# DZ60_Demoboard_V10_DLN18703.net
KiCad netlist of a schematic drawn in EAGLE
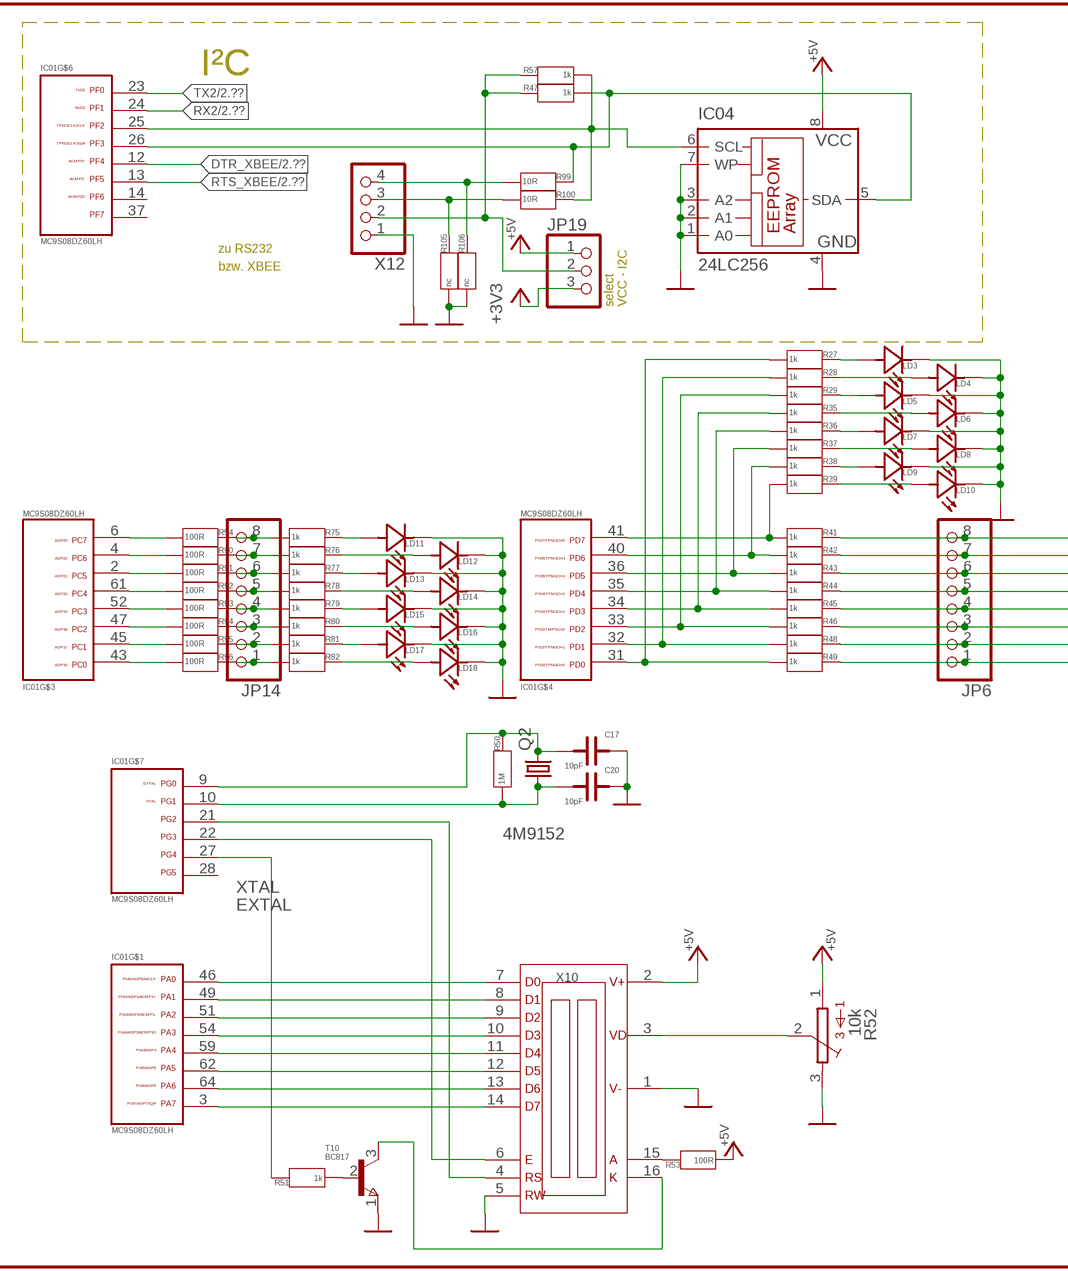
[diagram p0: schematic, sheet 1, part 1 of 2]
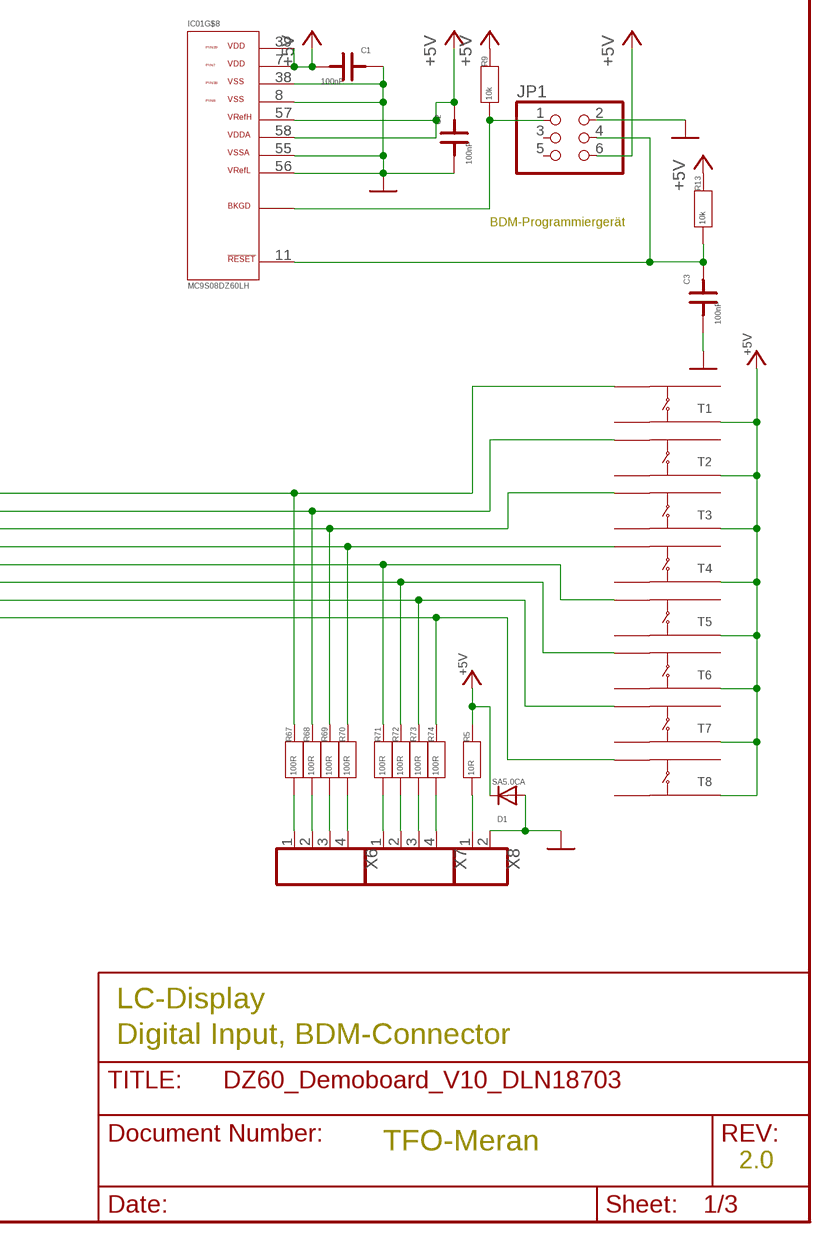
[diagram p1: schematic, sheet 1, part 2 of 2]
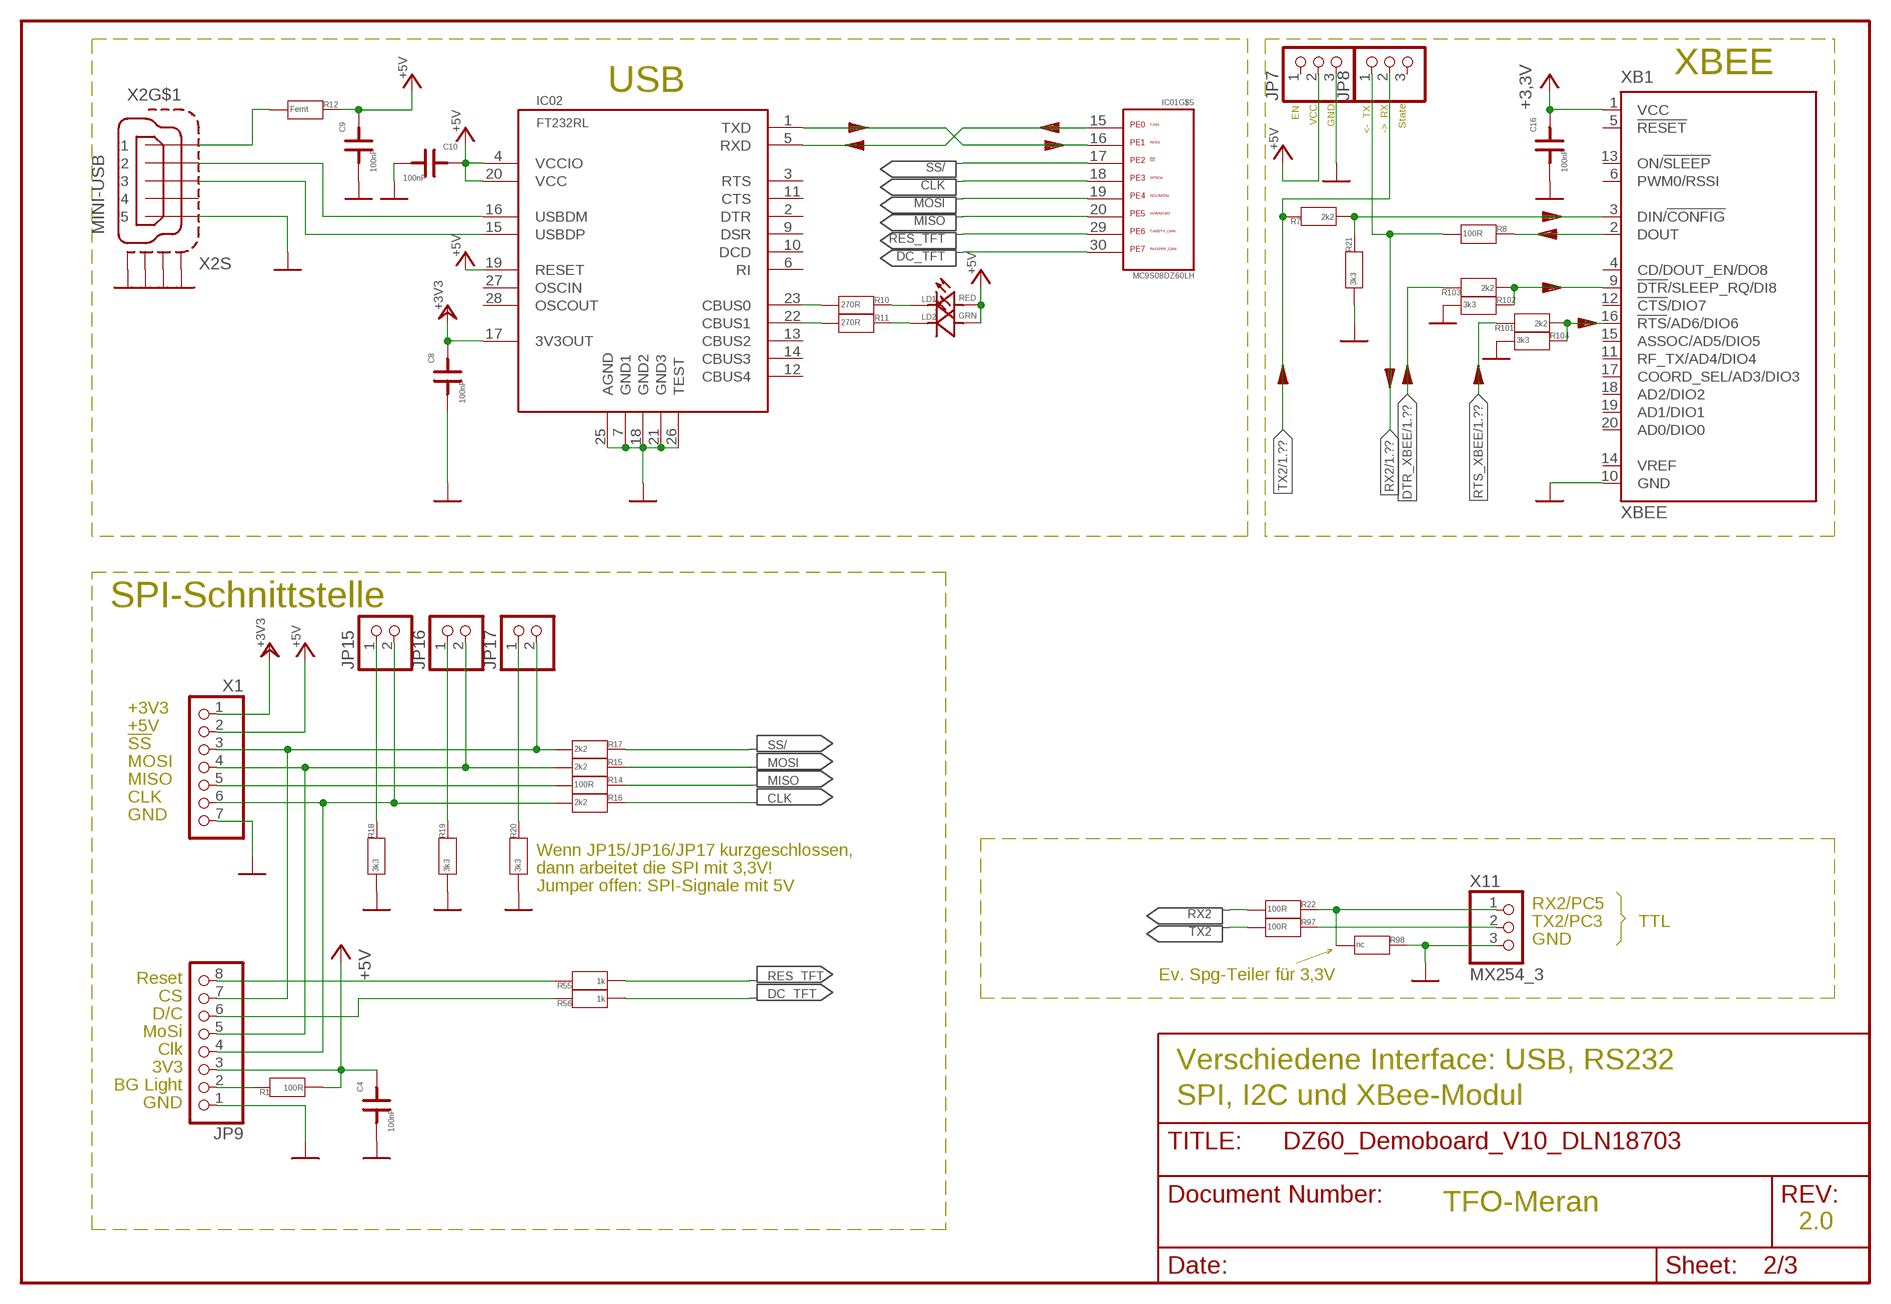
[diagram p2: schematic, sheet 2]
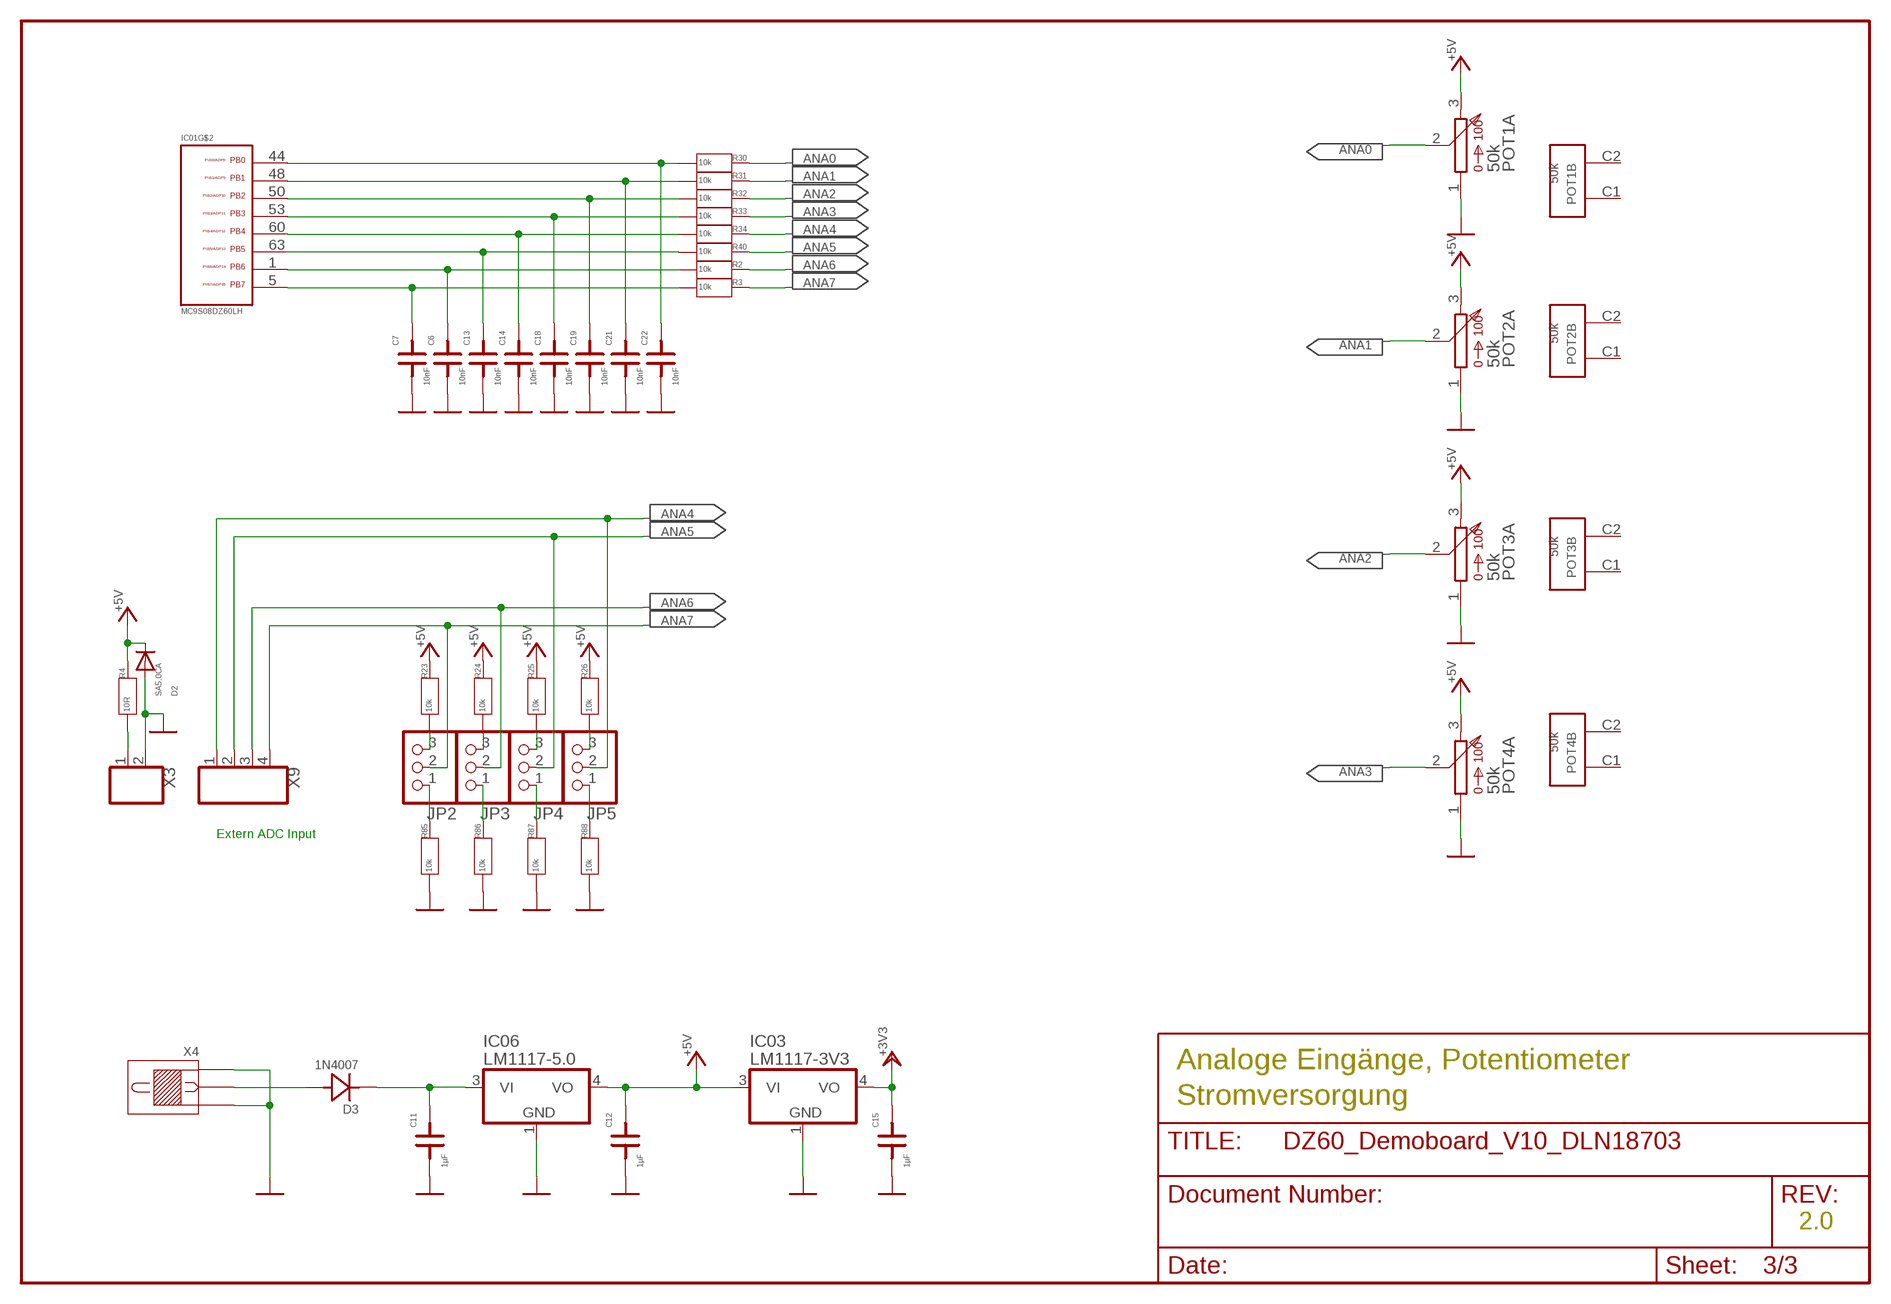
[diagram p3: schematic, sheet 3]

(export (version "E")
  (design (tool "Eeschema 10.0.6"))
  (components
    (comp (ref "C1")
      (value "100nF")
      (footprint "eagle-import:0805F")
      (libsource (lib "eagle-import") (part "C1"))
    )
    (comp (ref "C2")
      (value "100nF")
      (footprint "eagle-import:0805F")
      (libsource (lib "eagle-import") (part "C1"))
    )
    (comp (ref "C3")
      (value "100nF")
      (footprint "eagle-import:0805F")
      (libsource (lib "eagle-import") (part "C1"))
    )
    (comp (ref "C17")
      (value "10pF")
      (footprint "eagle-import:0805F")
      (libsource (lib "eagle-import") (part "C1"))
    )
    (comp (ref "C20")
      (value "10pF")
      (footprint "eagle-import:0805F")
      (libsource (lib "eagle-import") (part "C1"))
    )
    (comp (ref "D1")
      (value "SA5.0CA")
      (footprint "eagle-import:SMB")
      (libsource (lib "eagle-import") (part "DIODE-SMB"))
    )
    (comp (ref "IC01")
      (value "MC9S08DZ60LH")
      (footprint "eagle-import:LQFP64")
      (libsource (lib "eagle-import") (part "MC9S08DZ60LH"))
    )
    (comp (ref "IC04")
      (value "24LC256")
      (footprint "eagle-import:SO-08M")
      (libsource (lib "eagle-import") (part "24CSMLC256"))
    )
    (comp (ref "JP1")
      (value "PINHD-2X3")
      (footprint "eagle-import:2X03")
      (libsource (lib "eagle-import") (part "PINHD-2X3"))
    )
    (comp (ref "JP6")
      (value "PINHD-1X8")
      (footprint "eagle-import:1X08")
      (libsource (lib "eagle-import") (part "PINHD-1X8"))
    )
    (comp (ref "JP14")
      (value "PINHD-1X8")
      (footprint "eagle-import:1X08")
      (libsource (lib "eagle-import") (part "PINHD-1X8"))
    )
    (comp (ref "JP19")
      (value "PINHD-1X3")
      (footprint "eagle-import:1X03")
      (libsource (lib "eagle-import") (part "PINHD-1X3"))
    )
    (comp (ref "LD3")
      (value "LEDSMD")
      (footprint "eagle-import:0805LED")
      (libsource (lib "eagle-import") (part "LEDSMD"))
    )
    (comp (ref "LD4")
      (value "LEDSMD")
      (footprint "eagle-import:0805LED")
      (libsource (lib "eagle-import") (part "LEDSMD"))
    )
    (comp (ref "LD5")
      (value "LEDSMD")
      (footprint "eagle-import:0805LED")
      (libsource (lib "eagle-import") (part "LEDSMD"))
    )
    (comp (ref "LD6")
      (value "LEDSMD")
      (footprint "eagle-import:0805LED")
      (libsource (lib "eagle-import") (part "LEDSMD"))
    )
    (comp (ref "LD7")
      (value "LEDSMD")
      (footprint "eagle-import:0805LED")
      (libsource (lib "eagle-import") (part "LEDSMD"))
    )
    (comp (ref "LD8")
      (value "LEDSMD")
      (footprint "eagle-import:0805LED")
      (libsource (lib "eagle-import") (part "LEDSMD"))
    )
    (comp (ref "LD9")
      (value "LEDSMD")
      (footprint "eagle-import:0805LED")
      (libsource (lib "eagle-import") (part "LEDSMD"))
    )
    (comp (ref "LD10")
      (value "LEDSMD")
      (footprint "eagle-import:0805LED")
      (libsource (lib "eagle-import") (part "LEDSMD"))
    )
    (comp (ref "LD11")
      (value "LEDSMD")
      (footprint "eagle-import:0805LED")
      (libsource (lib "eagle-import") (part "LEDSMD"))
    )
    (comp (ref "LD12")
      (value "LEDSMD")
      (footprint "eagle-import:0805LED")
      (libsource (lib "eagle-import") (part "LEDSMD"))
    )
    (comp (ref "LD13")
      (value "LEDSMD")
      (footprint "eagle-import:0805LED")
      (libsource (lib "eagle-import") (part "LEDSMD"))
    )
    (comp (ref "LD14")
      (value "LEDSMD")
      (footprint "eagle-import:0805LED")
      (libsource (lib "eagle-import") (part "LEDSMD"))
    )
    (comp (ref "LD15")
      (value "LEDSMD")
      (footprint "eagle-import:0805LED")
      (libsource (lib "eagle-import") (part "LEDSMD"))
    )
    (comp (ref "LD16")
      (value "LEDSMD")
      (footprint "eagle-import:0805LED")
      (libsource (lib "eagle-import") (part "LEDSMD"))
    )
    (comp (ref "LD17")
      (value "LEDSMD")
      (footprint "eagle-import:0805LED")
      (libsource (lib "eagle-import") (part "LEDSMD"))
    )
    (comp (ref "LD18")
      (value "LEDSMD")
      (footprint "eagle-import:0805LED")
      (libsource (lib "eagle-import") (part "LEDSMD"))
    )
    (comp (ref "Q2")
      (value "4M9152")
      (footprint "eagle-import:HC49UP")
      (libsource (lib "eagle-import") (part "HC49UP"))
    )
    (comp (ref "R5")
      (value "10R")
      (footprint "eagle-import:0805")
      (libsource (lib "eagle-import") (part "R1"))
    )
    (comp (ref "R9")
      (value "10k")
      (footprint "eagle-import:0805")
      (libsource (lib "eagle-import") (part "R1"))
    )
    (comp (ref "R13")
      (value "10k")
      (footprint "eagle-import:0805")
      (libsource (lib "eagle-import") (part "R1"))
    )
    (comp (ref "R27")
      (value "1k")
      (footprint "eagle-import:0805")
      (libsource (lib "eagle-import") (part "R1"))
    )
    (comp (ref "R28")
      (value "1k")
      (footprint "eagle-import:0805")
      (libsource (lib "eagle-import") (part "R1"))
    )
    (comp (ref "R29")
      (value "1k")
      (footprint "eagle-import:0805")
      (libsource (lib "eagle-import") (part "R1"))
    )
    (comp (ref "R35")
      (value "1k")
      (footprint "eagle-import:0805")
      (libsource (lib "eagle-import") (part "R1"))
    )
    (comp (ref "R36")
      (value "1k")
      (footprint "eagle-import:0805")
      (libsource (lib "eagle-import") (part "R1"))
    )
    (comp (ref "R37")
      (value "1k")
      (footprint "eagle-import:0805")
      (libsource (lib "eagle-import") (part "R1"))
    )
    (comp (ref "R38")
      (value "1k")
      (footprint "eagle-import:0805")
      (libsource (lib "eagle-import") (part "R1"))
    )
    (comp (ref "R39")
      (value "1k")
      (footprint "eagle-import:0805")
      (libsource (lib "eagle-import") (part "R1"))
    )
    (comp (ref "R41")
      (value "1k")
      (footprint "eagle-import:0805")
      (libsource (lib "eagle-import") (part "R1"))
    )
    (comp (ref "R42")
      (value "1k")
      (footprint "eagle-import:0805")
      (libsource (lib "eagle-import") (part "R1"))
    )
    (comp (ref "R43")
      (value "1k")
      (footprint "eagle-import:0805")
      (libsource (lib "eagle-import") (part "R1"))
    )
    (comp (ref "R44")
      (value "1k")
      (footprint "eagle-import:0805")
      (libsource (lib "eagle-import") (part "R1"))
    )
    (comp (ref "R45")
      (value "1k")
      (footprint "eagle-import:0805")
      (libsource (lib "eagle-import") (part "R1"))
    )
    (comp (ref "R46")
      (value "1k")
      (footprint "eagle-import:0805")
      (libsource (lib "eagle-import") (part "R1"))
    )
    (comp (ref "R47")
      (value "1k")
      (footprint "eagle-import:0805")
      (libsource (lib "eagle-import") (part "R1"))
    )
    (comp (ref "R48")
      (value "1k")
      (footprint "eagle-import:0805")
      (libsource (lib "eagle-import") (part "R1"))
    )
    (comp (ref "R49")
      (value "1k")
      (footprint "eagle-import:0805")
      (libsource (lib "eagle-import") (part "R1"))
    )
    (comp (ref "R50")
      (value "1M")
      (footprint "eagle-import:0805")
      (libsource (lib "eagle-import") (part "R1"))
    )
    (comp (ref "R51")
      (value "1k")
      (footprint "eagle-import:0805")
      (libsource (lib "eagle-import") (part "R1"))
    )
    (comp (ref "R52")
      (value "10k")
      (footprint "eagle-import:S63X")
      (libsource (lib "eagle-import") (part "S63X"))
    )
    (comp (ref "R53")
      (value "100R")
      (footprint "eagle-import:0805")
      (libsource (lib "eagle-import") (part "R1"))
    )
    (comp (ref "R54")
      (value "100R")
      (footprint "eagle-import:0805")
      (libsource (lib "eagle-import") (part "R1"))
    )
    (comp (ref "R57")
      (value "1k")
      (footprint "eagle-import:0805")
      (libsource (lib "eagle-import") (part "R1"))
    )
    (comp (ref "R67")
      (value "100R")
      (footprint "eagle-import:0805")
      (libsource (lib "eagle-import") (part "R1"))
    )
    (comp (ref "R68")
      (value "100R")
      (footprint "eagle-import:0805")
      (libsource (lib "eagle-import") (part "R1"))
    )
    (comp (ref "R69")
      (value "100R")
      (footprint "eagle-import:0805")
      (libsource (lib "eagle-import") (part "R1"))
    )
    (comp (ref "R70")
      (value "100R")
      (footprint "eagle-import:0805")
      (libsource (lib "eagle-import") (part "R1"))
    )
    (comp (ref "R71")
      (value "100R")
      (footprint "eagle-import:0805")
      (libsource (lib "eagle-import") (part "R1"))
    )
    (comp (ref "R72")
      (value "100R")
      (footprint "eagle-import:0805")
      (libsource (lib "eagle-import") (part "R1"))
    )
    (comp (ref "R73")
      (value "100R")
      (footprint "eagle-import:0805")
      (libsource (lib "eagle-import") (part "R1"))
    )
    (comp (ref "R74")
      (value "100R")
      (footprint "eagle-import:0805")
      (libsource (lib "eagle-import") (part "R1"))
    )
    (comp (ref "R75")
      (value "1k")
      (footprint "eagle-import:0805")
      (libsource (lib "eagle-import") (part "R1"))
    )
    (comp (ref "R76")
      (value "1k")
      (footprint "eagle-import:0805")
      (libsource (lib "eagle-import") (part "R1"))
    )
    (comp (ref "R77")
      (value "1k")
      (footprint "eagle-import:0805")
      (libsource (lib "eagle-import") (part "R1"))
    )
    (comp (ref "R78")
      (value "1k")
      (footprint "eagle-import:0805")
      (libsource (lib "eagle-import") (part "R1"))
    )
    (comp (ref "R79")
      (value "1k")
      (footprint "eagle-import:0805")
      (libsource (lib "eagle-import") (part "R1"))
    )
    (comp (ref "R80")
      (value "1k")
      (footprint "eagle-import:0805")
      (libsource (lib "eagle-import") (part "R1"))
    )
    (comp (ref "R81")
      (value "1k")
      (footprint "eagle-import:0805")
      (libsource (lib "eagle-import") (part "R1"))
    )
    (comp (ref "R82")
      (value "1k")
      (footprint "eagle-import:0805")
      (libsource (lib "eagle-import") (part "R1"))
    )
    (comp (ref "R90")
      (value "100R")
      (footprint "eagle-import:0805")
      (libsource (lib "eagle-import") (part "R1"))
    )
    (comp (ref "R91")
      (value "100R")
      (footprint "eagle-import:0805")
      (libsource (lib "eagle-import") (part "R1"))
    )
    (comp (ref "R92")
      (value "100R")
      (footprint "eagle-import:0805")
      (libsource (lib "eagle-import") (part "R1"))
    )
    (comp (ref "R93")
      (value "100R")
      (footprint "eagle-import:0805")
      (libsource (lib "eagle-import") (part "R1"))
    )
    (comp (ref "R94")
      (value "100R")
      (footprint "eagle-import:0805")
      (libsource (lib "eagle-import") (part "R1"))
    )
    (comp (ref "R95")
      (value "100R")
      (footprint "eagle-import:0805")
      (libsource (lib "eagle-import") (part "R1"))
    )
    (comp (ref "R96")
      (value "100R")
      (footprint "eagle-import:0805")
      (libsource (lib "eagle-import") (part "R1"))
    )
    (comp (ref "R99")
      (value "10R")
      (footprint "eagle-import:0805")
      (libsource (lib "eagle-import") (part "R1"))
    )
    (comp (ref "R100")
      (value "10R")
      (footprint "eagle-import:0805")
      (libsource (lib "eagle-import") (part "R1"))
    )
    (comp (ref "R105")
      (value "nc")
      (footprint "eagle-import:0805")
      (libsource (lib "eagle-import") (part "R1"))
    )
    (comp (ref "R106")
      (value "nc")
      (footprint "eagle-import:0805")
      (libsource (lib "eagle-import") (part "R1"))
    )
    (comp (ref "T1")
      (value "TASTERTHT")
      (footprint "eagle-import:TASTE_THT")
      (libsource (lib "eagle-import") (part "TASTERTHT"))
    )
    (comp (ref "T2")
      (value "TASTERTHT")
      (footprint "eagle-import:TASTE_THT")
      (libsource (lib "eagle-import") (part "TASTERTHT"))
    )
    (comp (ref "T3")
      (value "TASTERTHT")
      (footprint "eagle-import:TASTE_THT")
      (libsource (lib "eagle-import") (part "TASTERTHT"))
    )
    (comp (ref "T4")
      (value "TASTERTHT")
      (footprint "eagle-import:TASTE_THT")
      (libsource (lib "eagle-import") (part "TASTERTHT"))
    )
    (comp (ref "T5")
      (value "TASTERTHT")
      (footprint "eagle-import:TASTE_THT")
      (libsource (lib "eagle-import") (part "TASTERTHT"))
    )
    (comp (ref "T6")
      (value "TASTERTHT")
      (footprint "eagle-import:TASTE_THT")
      (libsource (lib "eagle-import") (part "TASTERTHT"))
    )
    (comp (ref "T7")
      (value "TASTERTHT")
      (footprint "eagle-import:TASTE_THT")
      (libsource (lib "eagle-import") (part "TASTERTHT"))
    )
    (comp (ref "T8")
      (value "TASTERTHT")
      (footprint "eagle-import:TASTE_THT")
      (libsource (lib "eagle-import") (part "TASTERTHT"))
    )
    (comp (ref "T10")
      (value "BC817")
      (footprint "eagle-import:SOT-23")
      (libsource (lib "eagle-import") (part "BC817"))
    )
    (comp (ref "X6")
      (value "KLEMME4")
      (footprint "eagle-import:KLEMME4")
      (libsource (lib "eagle-import") (part "KLEMME4"))
    )
    (comp (ref "X7")
      (value "KLEMME4")
      (footprint "eagle-import:KLEMME4")
      (libsource (lib "eagle-import") (part "KLEMME4"))
    )
    (comp (ref "X8")
      (value "KLEMME2")
      (footprint "eagle-import:KLEMME2")
      (libsource (lib "eagle-import") (part "KLEMME2"))
    )
    (comp (ref "X10")
      (value "FDCC1602G")
      (footprint "eagle-import:FDCC1602G")
      (libsource (lib "eagle-import") (part "FDCC1602G"))
    )
    (comp (ref "X12")
      (value "MX254_4")
      (footprint "eagle-import:MX4")
      (libsource (lib "eagle-import") (part "MX254_4"))
    )
    (comp (ref "C4")
      (value "100nF")
      (footprint "eagle-import:0805F")
      (libsource (lib "eagle-import") (part "C1"))
    )
    (comp (ref "C8")
      (value "100nF")
      (footprint "eagle-import:0805F")
      (libsource (lib "eagle-import") (part "C1"))
    )
    (comp (ref "C9")
      (value "100nF")
      (footprint "eagle-import:0805F")
      (libsource (lib "eagle-import") (part "C1"))
    )
    (comp (ref "C10")
      (value "100nF")
      (footprint "eagle-import:0805F")
      (libsource (lib "eagle-import") (part "C1"))
    )
    (comp (ref "C16")
      (value "100nF")
      (footprint "eagle-import:0805F")
      (libsource (lib "eagle-import") (part "C1"))
    )
    (comp (ref "IC02")
      (value "FT232RL")
      (footprint "eagle-import:SSOP28")
      (libsource (lib "eagle-import") (part "FTDI232RL"))
    )
    (comp (ref "JP7")
      (value "PINHD-1X3")
      (footprint "eagle-import:1X03")
      (libsource (lib "eagle-import") (part "PINHD-1X3"))
    )
    (comp (ref "JP8")
      (value "PINHD-1X3")
      (footprint "eagle-import:1X03")
      (libsource (lib "eagle-import") (part "PINHD-1X3"))
    )
    (comp (ref "JP9")
      (value "PINHD-1X8")
      (footprint "eagle-import:1X08")
      (libsource (lib "eagle-import") (part "PINHD-1X8"))
    )
    (comp (ref "JP15")
      (value "PINHD-1X2")
      (footprint "eagle-import:1X02")
      (libsource (lib "eagle-import") (part "PINHD-1X2"))
    )
    (comp (ref "JP16")
      (value "PINHD-1X2")
      (footprint "eagle-import:1X02")
      (libsource (lib "eagle-import") (part "PINHD-1X2"))
    )
    (comp (ref "JP17")
      (value "PINHD-1X2")
      (footprint "eagle-import:1X02")
      (libsource (lib "eagle-import") (part "PINHD-1X2"))
    )
    (comp (ref "LD1")
      (value "RED")
      (footprint "eagle-import:0805LED")
      (libsource (lib "eagle-import") (part "LEDSMD"))
    )
    (comp (ref "LD2")
      (value "GRN")
      (footprint "eagle-import:0805LED")
      (libsource (lib "eagle-import") (part "LEDSMD"))
    )
    (comp (ref "R1")
      (value "100R")
      (footprint "eagle-import:0805")
      (libsource (lib "eagle-import") (part "R1"))
    )
    (comp (ref "R7")
      (value "2k2")
      (footprint "eagle-import:0805")
      (libsource (lib "eagle-import") (part "R1"))
    )
    (comp (ref "R8")
      (value "100R")
      (footprint "eagle-import:0805")
      (libsource (lib "eagle-import") (part "R1"))
    )
    (comp (ref "R10")
      (value "270R")
      (footprint "eagle-import:0805")
      (libsource (lib "eagle-import") (part "R1"))
    )
    (comp (ref "R11")
      (value "270R")
      (footprint "eagle-import:0805")
      (libsource (lib "eagle-import") (part "R1"))
    )
    (comp (ref "R12")
      (value "Ferrit")
      (footprint "eagle-import:1206")
      (libsource (lib "eagle-import") (part "R2"))
    )
    (comp (ref "R14")
      (value "100R")
      (footprint "eagle-import:0805")
      (libsource (lib "eagle-import") (part "R1"))
    )
    (comp (ref "R15")
      (value "2k2")
      (footprint "eagle-import:0805")
      (libsource (lib "eagle-import") (part "R1"))
    )
    (comp (ref "R16")
      (value "2k2")
      (footprint "eagle-import:0805")
      (libsource (lib "eagle-import") (part "R1"))
    )
    (comp (ref "R17")
      (value "2k2")
      (footprint "eagle-import:0805")
      (libsource (lib "eagle-import") (part "R1"))
    )
    (comp (ref "R18")
      (value "3k3")
      (footprint "eagle-import:0805")
      (libsource (lib "eagle-import") (part "R1"))
    )
    (comp (ref "R19")
      (value "3k3")
      (footprint "eagle-import:0805")
      (libsource (lib "eagle-import") (part "R1"))
    )
    (comp (ref "R20")
      (value "3k3")
      (footprint "eagle-import:0805")
      (libsource (lib "eagle-import") (part "R1"))
    )
    (comp (ref "R21")
      (value "3k3")
      (footprint "eagle-import:0805")
      (libsource (lib "eagle-import") (part "R1"))
    )
    (comp (ref "R22")
      (value "100R")
      (footprint "eagle-import:0805")
      (libsource (lib "eagle-import") (part "R1"))
    )
    (comp (ref "R55")
      (value "1k")
      (footprint "eagle-import:0805")
      (libsource (lib "eagle-import") (part "R1"))
    )
    (comp (ref "R56")
      (value "1k")
      (footprint "eagle-import:0805")
      (libsource (lib "eagle-import") (part "R1"))
    )
    (comp (ref "R97")
      (value "100R")
      (footprint "eagle-import:0805")
      (libsource (lib "eagle-import") (part "R1"))
    )
    (comp (ref "R98")
      (value "nc")
      (footprint "eagle-import:0805")
      (libsource (lib "eagle-import") (part "R1"))
    )
    (comp (ref "R101")
      (value "2k2")
      (footprint "eagle-import:0805")
      (libsource (lib "eagle-import") (part "R1"))
    )
    (comp (ref "R102")
      (value "3k3")
      (footprint "eagle-import:0805")
      (libsource (lib "eagle-import") (part "R1"))
    )
    (comp (ref "R103")
      (value "2k2")
      (footprint "eagle-import:0805")
      (libsource (lib "eagle-import") (part "R1"))
    )
    (comp (ref "R104")
      (value "3k3")
      (footprint "eagle-import:0805")
      (libsource (lib "eagle-import") (part "R1"))
    )
    (comp (ref "X1")
      (value "MX254_7")
      (footprint "eagle-import:MX7")
      (libsource (lib "eagle-import") (part "MX254_7"))
    )
    (comp (ref "X2")
      (value "MINI-USB")
      (footprint "eagle-import:32005-201")
      (libsource (lib "eagle-import") (part "MINI-USB-SCHIELD-32005-201"))
    )
    (comp (ref "X11")
      (value "MX254_3")
      (footprint "eagle-import:MX3")
      (libsource (lib "eagle-import") (part "MX254_3"))
    )
    (comp (ref "XB1")
      (value "XBEE")
      (footprint "eagle-import:XBEE")
      (fields (field (name "MPN") "XBP24-Z7UIT-004"))
      (libsource (lib "eagle-import") (part "XBEE"))
    )
    (comp (ref "C6")
      (value "10nF")
      (footprint "eagle-import:0805F")
      (libsource (lib "eagle-import") (part "C1"))
    )
    (comp (ref "C7")
      (value "10nF")
      (footprint "eagle-import:0805F")
      (libsource (lib "eagle-import") (part "C1"))
    )
    (comp (ref "C11")
      (value "1µF")
      (footprint "eagle-import:0805F")
      (libsource (lib "eagle-import") (part "C1"))
    )
    (comp (ref "C12")
      (value "1µF")
      (footprint "eagle-import:0805F")
      (libsource (lib "eagle-import") (part "C1"))
    )
    (comp (ref "C13")
      (value "10nF")
      (footprint "eagle-import:0805F")
      (libsource (lib "eagle-import") (part "C1"))
    )
    (comp (ref "C14")
      (value "10nF")
      (footprint "eagle-import:0805F")
      (libsource (lib "eagle-import") (part "C1"))
    )
    (comp (ref "C15")
      (value "1µF")
      (footprint "eagle-import:0805F")
      (libsource (lib "eagle-import") (part "C1"))
    )
    (comp (ref "C18")
      (value "10nF")
      (footprint "eagle-import:0805F")
      (libsource (lib "eagle-import") (part "C1"))
    )
    (comp (ref "C19")
      (value "10nF")
      (footprint "eagle-import:0805F")
      (libsource (lib "eagle-import") (part "C1"))
    )
    (comp (ref "C21")
      (value "10nF")
      (footprint "eagle-import:0805F")
      (libsource (lib "eagle-import") (part "C1"))
    )
    (comp (ref "C22")
      (value "10nF")
      (footprint "eagle-import:0805F")
      (libsource (lib "eagle-import") (part "C1"))
    )
    (comp (ref "D2")
      (value "SA5.0CA")
      (footprint "eagle-import:SMB")
      (libsource (lib "eagle-import") (part "DIODE-SMB"))
    )
    (comp (ref "D3")
      (value "1N4007")
      (footprint "eagle-import:MELF_B")
      (libsource (lib "eagle-import") (part "DHCMELF"))
    )
    (comp (ref "IC03")
      (value "LM1117-3V3")
      (footprint "eagle-import:DPAK")
      (libsource (lib "eagle-import") (part "LM1117DT"))
    )
    (comp (ref "IC06")
      (value "LM1117-5.0")
      (footprint "eagle-import:DPAK")
      (libsource (lib "eagle-import") (part "LM1117DT"))
    )
    (comp (ref "JP2")
      (value "PINHD-1X3")
      (footprint "eagle-import:1X03")
      (libsource (lib "eagle-import") (part "PINHD-1X3"))
    )
    (comp (ref "JP3")
      (value "PINHD-1X3")
      (footprint "eagle-import:1X03")
      (libsource (lib "eagle-import") (part "PINHD-1X3"))
    )
    (comp (ref "JP4")
      (value "PINHD-1X3")
      (footprint "eagle-import:1X03")
      (libsource (lib "eagle-import") (part "PINHD-1X3"))
    )
    (comp (ref "JP5")
      (value "PINHD-1X3")
      (footprint "eagle-import:1X03")
      (libsource (lib "eagle-import") (part "PINHD-1X3"))
    )
    (comp (ref "POT1")
      (value "50k")
      (footprint "eagle-import:ALPS_VERTICAL")
      (libsource (lib "eagle-import") (part "ALPSVERT"))
    )
    (comp (ref "POT2")
      (value "50k")
      (footprint "eagle-import:ALPS_VERTICAL")
      (libsource (lib "eagle-import") (part "ALPSVERT"))
    )
    (comp (ref "POT3")
      (value "50k")
      (footprint "eagle-import:ALPS_VERTICAL")
      (libsource (lib "eagle-import") (part "ALPSVERT"))
    )
    (comp (ref "POT4")
      (value "50k")
      (footprint "eagle-import:ALPS_VERTICAL")
      (libsource (lib "eagle-import") (part "ALPSVERT"))
    )
    (comp (ref "R2")
      (value "10k")
      (footprint "eagle-import:0805")
      (libsource (lib "eagle-import") (part "R1"))
    )
    (comp (ref "R3")
      (value "10k")
      (footprint "eagle-import:0805")
      (libsource (lib "eagle-import") (part "R1"))
    )
    (comp (ref "R4")
      (value "10R")
      (footprint "eagle-import:0805")
      (libsource (lib "eagle-import") (part "R1"))
    )
    (comp (ref "R23")
      (value "10k")
      (footprint "eagle-import:0805")
      (libsource (lib "eagle-import") (part "R1"))
    )
    (comp (ref "R24")
      (value "10k")
      (footprint "eagle-import:0805")
      (libsource (lib "eagle-import") (part "R1"))
    )
    (comp (ref "R25")
      (value "10k")
      (footprint "eagle-import:0805")
      (libsource (lib "eagle-import") (part "R1"))
    )
    (comp (ref "R26")
      (value "10k")
      (footprint "eagle-import:0805")
      (libsource (lib "eagle-import") (part "R1"))
    )
    (comp (ref "R30")
      (value "10k")
      (footprint "eagle-import:0805")
      (libsource (lib "eagle-import") (part "R1"))
    )
    (comp (ref "R31")
      (value "10k")
      (footprint "eagle-import:0805")
      (libsource (lib "eagle-import") (part "R1"))
    )
    (comp (ref "R32")
      (value "10k")
      (footprint "eagle-import:0805")
      (libsource (lib "eagle-import") (part "R1"))
    )
    (comp (ref "R33")
      (value "10k")
      (footprint "eagle-import:0805")
      (libsource (lib "eagle-import") (part "R1"))
    )
    (comp (ref "R34")
      (value "10k")
      (footprint "eagle-import:0805")
      (libsource (lib "eagle-import") (part "R1"))
    )
    (comp (ref "R40")
      (value "10k")
      (footprint "eagle-import:0805")
      (libsource (lib "eagle-import") (part "R1"))
    )
    (comp (ref "R85")
      (value "10k")
      (footprint "eagle-import:0805")
      (libsource (lib "eagle-import") (part "R1"))
    )
    (comp (ref "R86")
      (value "10k")
      (footprint "eagle-import:0805")
      (libsource (lib "eagle-import") (part "R1"))
    )
    (comp (ref "R87")
      (value "10k")
      (footprint "eagle-import:0805")
      (libsource (lib "eagle-import") (part "R1"))
    )
    (comp (ref "R88")
      (value "10k")
      (footprint "eagle-import:0805")
      (libsource (lib "eagle-import") (part "R1"))
    )
    (comp (ref "X3")
      (value "KLEMME2")
      (footprint "eagle-import:KLEMME2")
      (libsource (lib "eagle-import") (part "KLEMME2"))
    )
    (comp (ref "X4")
      (value "SPP")
      (footprint "eagle-import:SPP")
      (libsource (lib "eagle-import") (part "SPP"))
    )
    (comp (ref "X9")
      (value "KLEMME4")
      (footprint "eagle-import:KLEMME4")
      (libsource (lib "eagle-import") (part "KLEMME4"))
    )
  )
  (nets
    (net (code "1") (name "+3V3") (class "Default")
      (node (ref "C15") (pin "2") (pinfunction "2_2") (pintype "bidirectional"))
      (node (ref "C16") (pin "2") (pinfunction "2_2") (pintype "bidirectional"))
      (node (ref "C8") (pin "2") (pinfunction "2_2") (pintype "bidirectional"))
      (node (ref "IC02") (pin "17") (pinfunction "3V3OUT_17") (pintype "bidirectional"))
      (node (ref "IC03") (pin "4") (pinfunction "VO_4") (pintype "output"))
      (node (ref "JP19") (pin "3") (pinfunction "3_3") (pintype "passive"))
      (node (ref "X1") (pin "1") (pinfunction "1_1") (pintype "passive"))
      (node (ref "XB1") (pin "1") (pinfunction "VCC_1") (pintype "power_in"))
    )
    (net (code "2") (name "+5V") (class "Default")
      (node (ref "C1") (pin "1") (pinfunction "1_1") (pintype "bidirectional"))
      (node (ref "C10") (pin "2") (pinfunction "2_2") (pintype "bidirectional"))
      (node (ref "C12") (pin "2") (pinfunction "2_2") (pintype "bidirectional"))
      (node (ref "C2") (pin "2") (pinfunction "2_2") (pintype "bidirectional"))
      (node (ref "C4") (pin "2") (pinfunction "2_2") (pintype "bidirectional"))
      (node (ref "C9") (pin "2") (pinfunction "2_2") (pintype "bidirectional"))
      (node (ref "D1") (pin "C") (pinfunction "C_C") (pintype "passive"))
      (node (ref "D2") (pin "C") (pinfunction "C_C") (pintype "passive"))
      (node (ref "IC01") (pin "39") (pinfunction "VDD_PIN39_39") (pintype "bidirectional"))
      (node (ref "IC01") (pin "57") (pinfunction "VREFH_57") (pintype "bidirectional"))
      (node (ref "IC01") (pin "58") (pinfunction "VDDA_58") (pintype "bidirectional"))
      (node (ref "IC01") (pin "7") (pinfunction "VDD_PIN7_7") (pintype "bidirectional"))
      (node (ref "IC02") (pin "19") (pinfunction "RESET_19") (pintype "bidirectional"))
      (node (ref "IC02") (pin "20") (pinfunction "VCC_20") (pintype "bidirectional"))
      (node (ref "IC02") (pin "4") (pinfunction "VCCIO_4") (pintype "bidirectional"))
      (node (ref "IC03") (pin "3") (pinfunction "VI_3") (pintype "input"))
      (node (ref "IC04") (pin "8") (pinfunction "VCC_8") (pintype "power_in"))
      (node (ref "IC06") (pin "4") (pinfunction "VO_4") (pintype "output"))
      (node (ref "JP1") (pin "6") (pinfunction "6_6") (pintype "passive"))
      (node (ref "JP19") (pin "1") (pinfunction "1_1") (pintype "passive"))
      (node (ref "JP7") (pin "2") (pinfunction "2_2") (pintype "passive"))
      (node (ref "JP9") (pin "3") (pinfunction "3_3") (pintype "passive"))
      (node (ref "LD1") (pin "A") (pinfunction "2_A") (pintype "bidirectional"))
      (node (ref "LD2") (pin "A") (pinfunction "2_A") (pintype "bidirectional"))
      (node (ref "POT1") (pin "3") (pinfunction "3_3") (pintype "passive"))
      (node (ref "POT2") (pin "3") (pinfunction "3_3") (pintype "passive"))
      (node (ref "POT3") (pin "3") (pinfunction "3_3") (pintype "passive"))
      (node (ref "POT4") (pin "3") (pinfunction "3_3") (pintype "passive"))
      (node (ref "R1") (pin "1") (pinfunction "1_1") (pintype "bidirectional"))
      (node (ref "R12") (pin "2") (pinfunction "2_2") (pintype "bidirectional"))
      (node (ref "R13") (pin "2") (pinfunction "2_2") (pintype "bidirectional"))
      (node (ref "R23") (pin "2") (pinfunction "2_2") (pintype "bidirectional"))
      (node (ref "R24") (pin "2") (pinfunction "2_2") (pintype "bidirectional"))
      (node (ref "R25") (pin "2") (pinfunction "2_2") (pintype "bidirectional"))
      (node (ref "R26") (pin "2") (pinfunction "2_2") (pintype "bidirectional"))
      (node (ref "R4") (pin "2") (pinfunction "2_2") (pintype "bidirectional"))
      (node (ref "R5") (pin "2") (pinfunction "2_2") (pintype "bidirectional"))
      (node (ref "R52") (pin "1") (pinfunction "1_1") (pintype "passive"))
      (node (ref "R53") (pin "1") (pinfunction "1_1") (pintype "bidirectional"))
      (node (ref "R9") (pin "2") (pinfunction "2_2") (pintype "bidirectional"))
      (node (ref "T1") (pin "A1") (pinfunction "A1_A1") (pintype "bidirectional"))
      (node (ref "T2") (pin "A1") (pinfunction "A1_A1") (pintype "bidirectional"))
      (node (ref "T3") (pin "A1") (pinfunction "A1_A1") (pintype "bidirectional"))
      (node (ref "T4") (pin "A1") (pinfunction "A1_A1") (pintype "bidirectional"))
      (node (ref "T5") (pin "A1") (pinfunction "A1_A1") (pintype "bidirectional"))
      (node (ref "T6") (pin "A1") (pinfunction "A1_A1") (pintype "bidirectional"))
      (node (ref "T7") (pin "A1") (pinfunction "A1_A1") (pintype "bidirectional"))
      (node (ref "T8") (pin "A1") (pinfunction "A1_A1") (pintype "bidirectional"))
      (node (ref "X1") (pin "2") (pinfunction "2_2") (pintype "passive"))
      (node (ref "X10") (pin "2") (pinfunction "V+_2") (pintype "bidirectional"))
    )
    (net (code "3") (name "ANA0") (class "Default")
      (node (ref "POT1") (pin "2") (pinfunction "2_2") (pintype "passive"))
      (node (ref "R30") (pin "2") (pinfunction "2_2") (pintype "bidirectional"))
    )
    (net (code "4") (name "ANA1") (class "Default")
      (node (ref "POT2") (pin "2") (pinfunction "2_2") (pintype "passive"))
      (node (ref "R31") (pin "2") (pinfunction "2_2") (pintype "bidirectional"))
    )
    (net (code "5") (name "ANA2") (class "Default")
      (node (ref "POT3") (pin "2") (pinfunction "2_2") (pintype "passive"))
      (node (ref "R32") (pin "2") (pinfunction "2_2") (pintype "bidirectional"))
    )
    (net (code "6") (name "ANA3") (class "Default")
      (node (ref "POT4") (pin "2") (pinfunction "2_2") (pintype "passive"))
      (node (ref "R33") (pin "2") (pinfunction "2_2") (pintype "bidirectional"))
    )
    (net (code "7") (name "ANA4") (class "Default")
      (node (ref "JP5") (pin "2") (pinfunction "2_2") (pintype "passive"))
      (node (ref "R34") (pin "2") (pinfunction "2_2") (pintype "bidirectional"))
      (node (ref "X9") (pin "1") (pinfunction "1_1") (pintype "bidirectional"))
    )
    (net (code "8") (name "ANA5") (class "Default")
      (node (ref "JP4") (pin "2") (pinfunction "2_2") (pintype "passive"))
      (node (ref "R40") (pin "2") (pinfunction "2_2") (pintype "bidirectional"))
      (node (ref "X9") (pin "2") (pinfunction "2_2") (pintype "bidirectional"))
    )
    (net (code "9") (name "ANA6") (class "Default")
      (node (ref "JP3") (pin "2") (pinfunction "2_2") (pintype "passive"))
      (node (ref "R2") (pin "2") (pinfunction "2_2") (pintype "bidirectional"))
      (node (ref "X9") (pin "3") (pinfunction "3_3") (pintype "bidirectional"))
    )
    (net (code "10") (name "ANA7") (class "Default")
      (node (ref "JP2") (pin "2") (pinfunction "2_2") (pintype "passive"))
      (node (ref "R3") (pin "2") (pinfunction "2_2") (pintype "bidirectional"))
      (node (ref "X9") (pin "4") (pinfunction "4_4") (pintype "bidirectional"))
    )
    (net (code "11") (name "CLK") (class "Default")
      (node (ref "IC01") (pin "18") (pinfunction "PE3_18") (pintype "bidirectional"))
      (node (ref "R16") (pin "2") (pinfunction "2_2") (pintype "bidirectional"))
    )
    (net (code "12") (name "DC_TFT") (class "Default")
      (node (ref "IC01") (pin "30") (pinfunction "PE7_30") (pintype "bidirectional"))
      (node (ref "R56") (pin "1") (pinfunction "1_1") (pintype "bidirectional"))
    )
    (net (code "13") (name "DTR_XBEE") (class "Default")
      (node (ref "IC01") (pin "12") (pinfunction "PF4_12") (pintype "bidirectional"))
      (node (ref "R103") (pin "2") (pinfunction "2_2") (pintype "bidirectional"))
    )
    (net (code "14") (name "EXTAL") (class "Default")
      (node (ref "C20") (pin "1") (pinfunction "1_1") (pintype "bidirectional"))
      (node (ref "IC01") (pin "10") (pinfunction "PG1_10") (pintype "bidirectional"))
      (node (ref "Q2") (pin "1") (pinfunction "1_1") (pintype "passive"))
      (node (ref "R50") (pin "1") (pinfunction "1_1") (pintype "bidirectional"))
    )
    (net (code "15") (name "GND") (class "Default")
      (node (ref "C1") (pin "2") (pinfunction "2_2") (pintype "bidirectional"))
      (node (ref "C10") (pin "1") (pinfunction "1_1") (pintype "bidirectional"))
      (node (ref "C11") (pin "1") (pinfunction "1_1") (pintype "bidirectional"))
      (node (ref "C12") (pin "1") (pinfunction "1_1") (pintype "bidirectional"))
      (node (ref "C13") (pin "1") (pinfunction "1_1") (pintype "bidirectional"))
      (node (ref "C14") (pin "1") (pinfunction "1_1") (pintype "bidirectional"))
      (node (ref "C15") (pin "1") (pinfunction "1_1") (pintype "bidirectional"))
      (node (ref "C16") (pin "1") (pinfunction "1_1") (pintype "bidirectional"))
      (node (ref "C17") (pin "2") (pinfunction "2_2") (pintype "bidirectional"))
      (node (ref "C18") (pin "1") (pinfunction "1_1") (pintype "bidirectional"))
      (node (ref "C19") (pin "1") (pinfunction "1_1") (pintype "bidirectional"))
      (node (ref "C2") (pin "1") (pinfunction "1_1") (pintype "bidirectional"))
      (node (ref "C20") (pin "2") (pinfunction "2_2") (pintype "bidirectional"))
      (node (ref "C21") (pin "1") (pinfunction "1_1") (pintype "bidirectional"))
      (node (ref "C22") (pin "1") (pinfunction "1_1") (pintype "bidirectional"))
      (node (ref "C3") (pin "1") (pinfunction "1_1") (pintype "bidirectional"))
      (node (ref "C4") (pin "1") (pinfunction "1_1") (pintype "bidirectional"))
      (node (ref "C6") (pin "1") (pinfunction "1_1") (pintype "bidirectional"))
      (node (ref "C7") (pin "1") (pinfunction "1_1") (pintype "bidirectional"))
      (node (ref "C8") (pin "1") (pinfunction "1_1") (pintype "bidirectional"))
      (node (ref "C9") (pin "1") (pinfunction "1_1") (pintype "bidirectional"))
      (node (ref "D1") (pin "A") (pinfunction "A_A") (pintype "passive"))
      (node (ref "D2") (pin "A") (pinfunction "A_A") (pintype "passive"))
      (node (ref "IC01") (pin "38") (pinfunction "VSS_PIN38_38") (pintype "bidirectional"))
      (node (ref "IC01") (pin "55") (pinfunction "VSSA_55") (pintype "bidirectional"))
      (node (ref "IC01") (pin "56") (pinfunction "VREFL_56") (pintype "bidirectional"))
      (node (ref "IC01") (pin "8") (pinfunction "VSS_PIN8_8") (pintype "bidirectional"))
      (node (ref "IC02") (pin "18") (pinfunction "GND2_18") (pintype "bidirectional"))
      (node (ref "IC02") (pin "21") (pinfunction "GND3_21") (pintype "bidirectional"))
      (node (ref "IC02") (pin "25") (pinfunction "AGND_25") (pintype "bidirectional"))
      (node (ref "IC02") (pin "26") (pinfunction "TEST_26") (pintype "bidirectional"))
      (node (ref "IC02") (pin "7") (pinfunction "GND1_7") (pintype "bidirectional"))
      (node (ref "IC03") (pin "1") (pinfunction "GND_1") (pintype "input"))
      (node (ref "IC04") (pin "1") (pinfunction "A0_1") (pintype "input"))
      (node (ref "IC04") (pin "2") (pinfunction "A1_2") (pintype "input"))
      (node (ref "IC04") (pin "3") (pinfunction "A2_3") (pintype "input"))
      (node (ref "IC04") (pin "4") (pinfunction "GND_4") (pintype "power_in"))
      (node (ref "IC04") (pin "7") (pinfunction "WP_7") (pintype "input"))
      (node (ref "IC06") (pin "1") (pinfunction "GND_1") (pintype "input"))
      (node (ref "JP1") (pin "2") (pinfunction "2_2") (pintype "passive"))
      (node (ref "JP7") (pin "3") (pinfunction "3_3") (pintype "passive"))
      (node (ref "JP9") (pin "1") (pinfunction "1_1") (pintype "passive"))
      (node (ref "LD10") (pin "K") (pinfunction "1_K") (pintype "bidirectional"))
      (node (ref "LD11") (pin "K") (pinfunction "1_K") (pintype "bidirectional"))
      (node (ref "LD12") (pin "K") (pinfunction "1_K") (pintype "bidirectional"))
      (node (ref "LD13") (pin "K") (pinfunction "1_K") (pintype "bidirectional"))
      (node (ref "LD14") (pin "K") (pinfunction "1_K") (pintype "bidirectional"))
      (node (ref "LD15") (pin "K") (pinfunction "1_K") (pintype "bidirectional"))
      (node (ref "LD16") (pin "K") (pinfunction "1_K") (pintype "bidirectional"))
      (node (ref "LD17") (pin "K") (pinfunction "1_K") (pintype "bidirectional"))
      (node (ref "LD18") (pin "K") (pinfunction "1_K") (pintype "bidirectional"))
      (node (ref "LD3") (pin "K") (pinfunction "1_K") (pintype "bidirectional"))
      (node (ref "LD4") (pin "K") (pinfunction "1_K") (pintype "bidirectional"))
      (node (ref "LD5") (pin "K") (pinfunction "1_K") (pintype "bidirectional"))
      (node (ref "LD6") (pin "K") (pinfunction "1_K") (pintype "bidirectional"))
      (node (ref "LD7") (pin "K") (pinfunction "1_K") (pintype "bidirectional"))
      (node (ref "LD8") (pin "K") (pinfunction "1_K") (pintype "bidirectional"))
      (node (ref "LD9") (pin "K") (pinfunction "1_K") (pintype "bidirectional"))
      (node (ref "POT1") (pin "1") (pinfunction "1_1") (pintype "passive"))
      (node (ref "POT2") (pin "1") (pinfunction "1_1") (pintype "passive"))
      (node (ref "POT3") (pin "1") (pinfunction "1_1") (pintype "passive"))
      (node (ref "POT4") (pin "1") (pinfunction "1_1") (pintype "passive"))
      (node (ref "R102") (pin "1") (pinfunction "1_1") (pintype "bidirectional"))
      (node (ref "R104") (pin "1") (pinfunction "1_1") (pintype "bidirectional"))
      (node (ref "R105") (pin "1") (pinfunction "1_1") (pintype "bidirectional"))
      (node (ref "R106") (pin "1") (pinfunction "1_1") (pintype "bidirectional"))
      (node (ref "R18") (pin "1") (pinfunction "1_1") (pintype "bidirectional"))
      (node (ref "R19") (pin "1") (pinfunction "1_1") (pintype "bidirectional"))
      (node (ref "R20") (pin "1") (pinfunction "1_1") (pintype "bidirectional"))
      (node (ref "R21") (pin "1") (pinfunction "1_1") (pintype "bidirectional"))
      (node (ref "R52") (pin "3") (pinfunction "3_3") (pintype "passive"))
      (node (ref "R85") (pin "1") (pinfunction "1_1") (pintype "bidirectional"))
      (node (ref "R86") (pin "1") (pinfunction "1_1") (pintype "bidirectional"))
      (node (ref "R87") (pin "1") (pinfunction "1_1") (pintype "bidirectional"))
      (node (ref "R88") (pin "1") (pinfunction "1_1") (pintype "bidirectional"))
      (node (ref "R98") (pin "2") (pinfunction "2_2") (pintype "bidirectional"))
      (node (ref "T10") (pin "1") (pinfunction "E_1") (pintype "passive"))
      (node (ref "X1") (pin "7") (pinfunction "7_7") (pintype "passive"))
      (node (ref "X10") (pin "1") (pinfunction "V-_1") (pintype "bidirectional"))
      (node (ref "X10") (pin "5") (pinfunction "RW_5") (pintype "bidirectional"))
      (node (ref "X11") (pin "3") (pinfunction "3_3") (pintype "passive"))
      (node (ref "X12") (pin "1") (pinfunction "1_1") (pintype "passive"))
      (node (ref "X2") (pin "5") (pinfunction "5_5") (pintype "passive"))
      (node (ref "X2") (pin "M1") (pinfunction "S1_M1") (pintype "passive"))
      (node (ref "X2") (pin "M2") (pinfunction "S2_M2") (pintype "passive"))
      (node (ref "X2") (pin "M3") (pinfunction "S3_M3") (pintype "passive"))
      (node (ref "X2") (pin "M4") (pinfunction "S4_M4") (pintype "passive"))
      (node (ref "X3") (pin "2") (pinfunction "2_2") (pintype "bidirectional"))
      (node (ref "X4") (pin "1") (pinfunction "1_1") (pintype "bidirectional"))
      (node (ref "X4") (pin "3") (pinfunction "3_3") (pintype "bidirectional"))
      (node (ref "X8") (pin "2") (pinfunction "2_2") (pintype "bidirectional"))
      (node (ref "XB1") (pin "10") (pinfunction "GND_10") (pintype "power_in"))
    )
    (net (code "16") (name "MISO") (class "Default")
      (node (ref "IC01") (pin "20") (pinfunction "PE5_20") (pintype "bidirectional"))
      (node (ref "R14") (pin "2") (pinfunction "2_2") (pintype "bidirectional"))
    )
    (net (code "17") (name "MOSI") (class "Default")
      (node (ref "IC01") (pin "19") (pinfunction "PE4_19") (pintype "bidirectional"))
      (node (ref "R15") (pin "2") (pinfunction "2_2") (pintype "bidirectional"))
    )
    (net (code "18") (name "Net-(D3-PadA)") (class "Default")
      (node (ref "D3") (pin "A") (pinfunction "A_A") (pintype "bidirectional"))
      (node (ref "X4") (pin "2") (pinfunction "2_2") (pintype "bidirectional"))
    )
    (net (code "19") (name "Net-(IC01A-PA0)") (class "Default")
      (node (ref "IC01") (pin "46") (pinfunction "PA0_46") (pintype "bidirectional"))
      (node (ref "X10") (pin "7") (pinfunction "D0_7") (pintype "bidirectional"))
    )
    (net (code "20") (name "Net-(IC01A-PA1)") (class "Default")
      (node (ref "IC01") (pin "49") (pinfunction "PA1_49") (pintype "bidirectional"))
      (node (ref "X10") (pin "8") (pinfunction "D1_8") (pintype "bidirectional"))
    )
    (net (code "21") (name "Net-(IC01A-PA2)") (class "Default")
      (node (ref "IC01") (pin "51") (pinfunction "PA2_51") (pintype "bidirectional"))
      (node (ref "X10") (pin "9") (pinfunction "D2_9") (pintype "bidirectional"))
    )
    (net (code "22") (name "Net-(IC01A-PA3)") (class "Default")
      (node (ref "IC01") (pin "54") (pinfunction "PA3_54") (pintype "bidirectional"))
      (node (ref "X10") (pin "10") (pinfunction "D3_10") (pintype "bidirectional"))
    )
    (net (code "23") (name "Net-(IC01A-PA4)") (class "Default")
      (node (ref "IC01") (pin "59") (pinfunction "PA4_59") (pintype "bidirectional"))
      (node (ref "X10") (pin "11") (pinfunction "D4_11") (pintype "bidirectional"))
    )
    (net (code "24") (name "Net-(IC01A-PA5)") (class "Default")
      (node (ref "IC01") (pin "62") (pinfunction "PA5_62") (pintype "bidirectional"))
      (node (ref "X10") (pin "12") (pinfunction "D5_12") (pintype "bidirectional"))
    )
    (net (code "25") (name "Net-(IC01A-PA6)") (class "Default")
      (node (ref "IC01") (pin "64") (pinfunction "PA6_64") (pintype "bidirectional"))
      (node (ref "X10") (pin "13") (pinfunction "D6_13") (pintype "bidirectional"))
    )
    (net (code "26") (name "Net-(IC01A-PA7)") (class "Default")
      (node (ref "IC01") (pin "3") (pinfunction "PA7_3") (pintype "bidirectional"))
      (node (ref "X10") (pin "14") (pinfunction "D7_14") (pintype "bidirectional"))
    )
    (net (code "27") (name "Net-(IC01B-PB0)") (class "Default")
      (node (ref "C22") (pin "2") (pinfunction "2_2") (pintype "bidirectional"))
      (node (ref "IC01") (pin "44") (pinfunction "PB0_44") (pintype "bidirectional"))
      (node (ref "R30") (pin "1") (pinfunction "1_1") (pintype "bidirectional"))
    )
    (net (code "28") (name "Net-(IC01B-PB1)") (class "Default")
      (node (ref "C21") (pin "2") (pinfunction "2_2") (pintype "bidirectional"))
      (node (ref "IC01") (pin "48") (pinfunction "PB1_48") (pintype "bidirectional"))
      (node (ref "R31") (pin "1") (pinfunction "1_1") (pintype "bidirectional"))
    )
    (net (code "29") (name "Net-(IC01B-PB2)") (class "Default")
      (node (ref "C19") (pin "2") (pinfunction "2_2") (pintype "bidirectional"))
      (node (ref "IC01") (pin "50") (pinfunction "PB2_50") (pintype "bidirectional"))
      (node (ref "R32") (pin "1") (pinfunction "1_1") (pintype "bidirectional"))
    )
    (net (code "30") (name "Net-(IC01B-PB3)") (class "Default")
      (node (ref "C18") (pin "2") (pinfunction "2_2") (pintype "bidirectional"))
      (node (ref "IC01") (pin "53") (pinfunction "PB3_53") (pintype "bidirectional"))
      (node (ref "R33") (pin "1") (pinfunction "1_1") (pintype "bidirectional"))
    )
    (net (code "31") (name "Net-(IC01B-PB4)") (class "Default")
      (node (ref "C14") (pin "2") (pinfunction "2_2") (pintype "bidirectional"))
      (node (ref "IC01") (pin "60") (pinfunction "PB4_60") (pintype "bidirectional"))
      (node (ref "R34") (pin "1") (pinfunction "1_1") (pintype "bidirectional"))
    )
    (net (code "32") (name "Net-(IC01B-PB5)") (class "Default")
      (node (ref "C13") (pin "2") (pinfunction "2_2") (pintype "bidirectional"))
      (node (ref "IC01") (pin "63") (pinfunction "PB5_63") (pintype "bidirectional"))
      (node (ref "R40") (pin "1") (pinfunction "1_1") (pintype "bidirectional"))
    )
    (net (code "33") (name "Net-(IC01B-PB6)") (class "Default")
      (node (ref "C6") (pin "2") (pinfunction "2_2") (pintype "bidirectional"))
      (node (ref "IC01") (pin "1") (pinfunction "PB6_1") (pintype "bidirectional"))
      (node (ref "R2") (pin "1") (pinfunction "1_1") (pintype "bidirectional"))
    )
    (net (code "34") (name "Net-(IC01B-PB7)") (class "Default")
      (node (ref "C7") (pin "2") (pinfunction "2_2") (pintype "bidirectional"))
      (node (ref "IC01") (pin "5") (pinfunction "PB7_5") (pintype "bidirectional"))
      (node (ref "R3") (pin "1") (pinfunction "1_1") (pintype "bidirectional"))
    )
    (net (code "35") (name "Net-(IC01C-PC0)") (class "Default")
      (node (ref "IC01") (pin "43") (pinfunction "PC0_43") (pintype "bidirectional"))
      (node (ref "R96") (pin "1") (pinfunction "1_1") (pintype "bidirectional"))
    )
    (net (code "36") (name "Net-(IC01C-PC1)") (class "Default")
      (node (ref "IC01") (pin "45") (pinfunction "PC1_45") (pintype "bidirectional"))
      (node (ref "R95") (pin "1") (pinfunction "1_1") (pintype "bidirectional"))
    )
    (net (code "37") (name "Net-(IC01C-PC2)") (class "Default")
      (node (ref "IC01") (pin "47") (pinfunction "PC2_47") (pintype "bidirectional"))
      (node (ref "R94") (pin "1") (pinfunction "1_1") (pintype "bidirectional"))
    )
    (net (code "38") (name "Net-(IC01C-PC3)") (class "Default")
      (node (ref "IC01") (pin "52") (pinfunction "PC3_52") (pintype "bidirectional"))
      (node (ref "R93") (pin "1") (pinfunction "1_1") (pintype "bidirectional"))
    )
    (net (code "39") (name "Net-(IC01C-PC4)") (class "Default")
      (node (ref "IC01") (pin "61") (pinfunction "PC4_61") (pintype "bidirectional"))
      (node (ref "R92") (pin "1") (pinfunction "1_1") (pintype "bidirectional"))
    )
    (net (code "40") (name "Net-(IC01C-PC5)") (class "Default")
      (node (ref "IC01") (pin "2") (pinfunction "PC5_2") (pintype "bidirectional"))
      (node (ref "R91") (pin "1") (pinfunction "1_1") (pintype "bidirectional"))
    )
    (net (code "41") (name "Net-(IC01C-PC6)") (class "Default")
      (node (ref "IC01") (pin "4") (pinfunction "PC6_4") (pintype "bidirectional"))
      (node (ref "R90") (pin "1") (pinfunction "1_1") (pintype "bidirectional"))
    )
    (net (code "42") (name "Net-(IC01C-PC7)") (class "Default")
      (node (ref "IC01") (pin "6") (pinfunction "PC7_6") (pintype "bidirectional"))
      (node (ref "R54") (pin "1") (pinfunction "1_1") (pintype "bidirectional"))
    )
    (net (code "43") (name "Net-(IC01D-PD0)") (class "Default")
      (node (ref "IC01") (pin "31") (pinfunction "PD0_31") (pintype "bidirectional"))
      (node (ref "R27") (pin "1") (pinfunction "1_1") (pintype "bidirectional"))
      (node (ref "R49") (pin "1") (pinfunction "1_1") (pintype "bidirectional"))
    )
    (net (code "44") (name "Net-(IC01D-PD1)") (class "Default")
      (node (ref "IC01") (pin "32") (pinfunction "PD1_32") (pintype "bidirectional"))
      (node (ref "R28") (pin "1") (pinfunction "1_1") (pintype "bidirectional"))
      (node (ref "R48") (pin "1") (pinfunction "1_1") (pintype "bidirectional"))
    )
    (net (code "45") (name "Net-(IC01D-PD2)") (class "Default")
      (node (ref "IC01") (pin "33") (pinfunction "PD2_33") (pintype "bidirectional"))
      (node (ref "R29") (pin "1") (pinfunction "1_1") (pintype "bidirectional"))
      (node (ref "R46") (pin "1") (pinfunction "1_1") (pintype "bidirectional"))
    )
    (net (code "46") (name "Net-(IC01D-PD3)") (class "Default")
      (node (ref "IC01") (pin "34") (pinfunction "PD3_34") (pintype "bidirectional"))
      (node (ref "R35") (pin "1") (pinfunction "1_1") (pintype "bidirectional"))
      (node (ref "R45") (pin "1") (pinfunction "1_1") (pintype "bidirectional"))
    )
    (net (code "47") (name "Net-(IC01D-PD4)") (class "Default")
      (node (ref "IC01") (pin "35") (pinfunction "PD4_35") (pintype "bidirectional"))
      (node (ref "R36") (pin "1") (pinfunction "1_1") (pintype "bidirectional"))
      (node (ref "R44") (pin "1") (pinfunction "1_1") (pintype "bidirectional"))
    )
    (net (code "48") (name "Net-(IC01D-PD5)") (class "Default")
      (node (ref "IC01") (pin "36") (pinfunction "PD5_36") (pintype "bidirectional"))
      (node (ref "R37") (pin "1") (pinfunction "1_1") (pintype "bidirectional"))
      (node (ref "R43") (pin "1") (pinfunction "1_1") (pintype "bidirectional"))
    )
    (net (code "49") (name "Net-(IC01D-PD6)") (class "Default")
      (node (ref "IC01") (pin "40") (pinfunction "PD6_40") (pintype "bidirectional"))
      (node (ref "R38") (pin "1") (pinfunction "1_1") (pintype "bidirectional"))
      (node (ref "R42") (pin "1") (pinfunction "1_1") (pintype "bidirectional"))
    )
    (net (code "50") (name "Net-(IC01D-PD7)") (class "Default")
      (node (ref "IC01") (pin "41") (pinfunction "PD7_41") (pintype "bidirectional"))
      (node (ref "R39") (pin "1") (pinfunction "1_1") (pintype "bidirectional"))
      (node (ref "R41") (pin "1") (pinfunction "1_1") (pintype "bidirectional"))
    )
    (net (code "51") (name "Net-(IC01E-PE0)") (class "Default")
      (node (ref "IC01") (pin "15") (pinfunction "PE0_15") (pintype "bidirectional"))
      (node (ref "IC02") (pin "5") (pinfunction "RXD_5") (pintype "bidirectional"))
    )
    (net (code "52") (name "Net-(IC01E-PE1)") (class "Default")
      (node (ref "IC01") (pin "16") (pinfunction "PE1_16") (pintype "bidirectional"))
      (node (ref "IC02") (pin "1") (pinfunction "TXD_1") (pintype "bidirectional"))
    )
    (net (code "53") (name "Net-(IC01F-PF2)") (class "Default")
      (node (ref "IC01") (pin "25") (pinfunction "PF2_25") (pintype "bidirectional"))
      (node (ref "IC04") (pin "6") (pinfunction "SCL_6") (pintype "input"))
      (node (ref "R100") (pin "2") (pinfunction "2_2") (pintype "bidirectional"))
      (node (ref "R57") (pin "1") (pinfunction "1_1") (pintype "bidirectional"))
    )
    (net (code "54") (name "Net-(IC01F-PF3)") (class "Default")
      (node (ref "IC01") (pin "26") (pinfunction "PF3_26") (pintype "bidirectional"))
      (node (ref "IC04") (pin "5") (pinfunction "SDA_5") (pintype "bidirectional"))
      (node (ref "R47") (pin "1") (pinfunction "1_1") (pintype "bidirectional"))
      (node (ref "R99") (pin "2") (pinfunction "2_2") (pintype "bidirectional"))
    )
    (net (code "55") (name "Net-(IC01G-PG2)") (class "Default")
      (node (ref "IC01") (pin "21") (pinfunction "PG2_21") (pintype "bidirectional"))
      (node (ref "X10") (pin "4") (pinfunction "RS_4") (pintype "bidirectional"))
    )
    (net (code "56") (name "Net-(IC01G-PG3)") (class "Default")
      (node (ref "IC01") (pin "22") (pinfunction "PG3_22") (pintype "bidirectional"))
      (node (ref "X10") (pin "6") (pinfunction "E_6") (pintype "bidirectional"))
    )
    (net (code "57") (name "Net-(IC01G-PG4)") (class "Default")
      (node (ref "IC01") (pin "27") (pinfunction "PG4_27") (pintype "bidirectional"))
      (node (ref "R51") (pin "2") (pinfunction "2_2") (pintype "bidirectional"))
    )
    (net (code "58") (name "Net-(IC01H-BKGD)") (class "Default")
      (node (ref "IC01") (pin "42") (pinfunction "BKGD_42") (pintype "bidirectional"))
      (node (ref "JP1") (pin "1") (pinfunction "1_1") (pintype "passive"))
      (node (ref "R9") (pin "1") (pinfunction "1_1") (pintype "bidirectional"))
    )
    (net (code "59") (name "Net-(IC01H-RST{slash})") (class "Default")
      (node (ref "C3") (pin "2") (pinfunction "2_2") (pintype "bidirectional"))
      (node (ref "IC01") (pin "11") (pinfunction "RST/_11") (pintype "bidirectional"))
      (node (ref "JP1") (pin "4") (pinfunction "4_4") (pintype "passive"))
      (node (ref "R13") (pin "1") (pinfunction "1_1") (pintype "bidirectional"))
    )
    (net (code "60") (name "Net-(IC02-CBUS0)") (class "Default")
      (node (ref "IC02") (pin "23") (pinfunction "CBUS0_23") (pintype "bidirectional"))
      (node (ref "R10") (pin "1") (pinfunction "1_1") (pintype "bidirectional"))
    )
    (net (code "61") (name "Net-(IC02-CBUS1)") (class "Default")
      (node (ref "IC02") (pin "22") (pinfunction "CBUS1_22") (pintype "bidirectional"))
      (node (ref "R11") (pin "1") (pinfunction "1_1") (pintype "bidirectional"))
    )
    (net (code "62") (name "Net-(IC02-USBDM)") (class "Default")
      (node (ref "IC02") (pin "16") (pinfunction "USBDM_16") (pintype "bidirectional"))
      (node (ref "X2") (pin "2") (pinfunction "2_2") (pintype "passive"))
    )
    (net (code "63") (name "Net-(IC02-USBDP)") (class "Default")
      (node (ref "IC02") (pin "15") (pinfunction "USBDP_15") (pintype "bidirectional"))
      (node (ref "X2") (pin "3") (pinfunction "3_3") (pintype "passive"))
    )
    (net (code "64") (name "Net-(IC06-VI)") (class "Default")
      (node (ref "C11") (pin "2") (pinfunction "2_2") (pintype "bidirectional"))
      (node (ref "D3") (pin "K") (pinfunction "K_K") (pintype "bidirectional"))
      (node (ref "IC06") (pin "3") (pinfunction "VI_3") (pintype "input"))
    )
    (net (code "65") (name "Net-(JP2-Pad1)") (class "Default")
      (node (ref "JP2") (pin "1") (pinfunction "1_1") (pintype "passive"))
      (node (ref "R85") (pin "2") (pinfunction "2_2") (pintype "bidirectional"))
    )
    (net (code "66") (name "Net-(JP2-Pad3)") (class "Default")
      (node (ref "JP2") (pin "3") (pinfunction "3_3") (pintype "passive"))
      (node (ref "R23") (pin "1") (pinfunction "1_1") (pintype "bidirectional"))
    )
    (net (code "67") (name "Net-(JP3-Pad1)") (class "Default")
      (node (ref "JP3") (pin "1") (pinfunction "1_1") (pintype "passive"))
      (node (ref "R86") (pin "2") (pinfunction "2_2") (pintype "bidirectional"))
    )
    (net (code "68") (name "Net-(JP3-Pad3)") (class "Default")
      (node (ref "JP3") (pin "3") (pinfunction "3_3") (pintype "passive"))
      (node (ref "R24") (pin "1") (pinfunction "1_1") (pintype "bidirectional"))
    )
    (net (code "69") (name "Net-(JP4-Pad1)") (class "Default")
      (node (ref "JP4") (pin "1") (pinfunction "1_1") (pintype "passive"))
      (node (ref "R87") (pin "2") (pinfunction "2_2") (pintype "bidirectional"))
    )
    (net (code "70") (name "Net-(JP4-Pad3)") (class "Default")
      (node (ref "JP4") (pin "3") (pinfunction "3_3") (pintype "passive"))
      (node (ref "R25") (pin "1") (pinfunction "1_1") (pintype "bidirectional"))
    )
    (net (code "71") (name "Net-(JP5-Pad1)") (class "Default")
      (node (ref "JP5") (pin "1") (pinfunction "1_1") (pintype "passive"))
      (node (ref "R88") (pin "2") (pinfunction "2_2") (pintype "bidirectional"))
    )
    (net (code "72") (name "Net-(JP5-Pad3)") (class "Default")
      (node (ref "JP5") (pin "3") (pinfunction "3_3") (pintype "passive"))
      (node (ref "R26") (pin "1") (pinfunction "1_1") (pintype "bidirectional"))
    )
    (net (code "73") (name "Net-(JP6-Pad1)") (class "Default")
      (node (ref "JP6") (pin "1") (pinfunction "1_1") (pintype "passive"))
      (node (ref "R49") (pin "2") (pinfunction "2_2") (pintype "bidirectional"))
      (node (ref "R74") (pin "2") (pinfunction "2_2") (pintype "bidirectional"))
      (node (ref "T8") (pin "B2") (pinfunction "B2_B2") (pintype "bidirectional"))
    )
    (net (code "74") (name "Net-(JP6-Pad2)") (class "Default")
      (node (ref "JP6") (pin "2") (pinfunction "2_2") (pintype "passive"))
      (node (ref "R48") (pin "2") (pinfunction "2_2") (pintype "bidirectional"))
      (node (ref "R73") (pin "2") (pinfunction "2_2") (pintype "bidirectional"))
      (node (ref "T7") (pin "B2") (pinfunction "B2_B2") (pintype "bidirectional"))
    )
    (net (code "75") (name "Net-(JP6-Pad3)") (class "Default")
      (node (ref "JP6") (pin "3") (pinfunction "3_3") (pintype "passive"))
      (node (ref "R46") (pin "2") (pinfunction "2_2") (pintype "bidirectional"))
      (node (ref "R72") (pin "2") (pinfunction "2_2") (pintype "bidirectional"))
      (node (ref "T6") (pin "B2") (pinfunction "B2_B2") (pintype "bidirectional"))
    )
    (net (code "76") (name "Net-(JP6-Pad4)") (class "Default")
      (node (ref "JP6") (pin "4") (pinfunction "4_4") (pintype "passive"))
      (node (ref "R45") (pin "2") (pinfunction "2_2") (pintype "bidirectional"))
      (node (ref "R71") (pin "2") (pinfunction "2_2") (pintype "bidirectional"))
      (node (ref "T5") (pin "B2") (pinfunction "B2_B2") (pintype "bidirectional"))
    )
    (net (code "77") (name "Net-(JP6-Pad5)") (class "Default")
      (node (ref "JP6") (pin "5") (pinfunction "5_5") (pintype "passive"))
      (node (ref "R44") (pin "2") (pinfunction "2_2") (pintype "bidirectional"))
      (node (ref "R70") (pin "2") (pinfunction "2_2") (pintype "bidirectional"))
      (node (ref "T4") (pin "B2") (pinfunction "B2_B2") (pintype "bidirectional"))
    )
    (net (code "78") (name "Net-(JP6-Pad6)") (class "Default")
      (node (ref "JP6") (pin "6") (pinfunction "6_6") (pintype "passive"))
      (node (ref "R43") (pin "2") (pinfunction "2_2") (pintype "bidirectional"))
      (node (ref "R69") (pin "2") (pinfunction "2_2") (pintype "bidirectional"))
      (node (ref "T3") (pin "B2") (pinfunction "B2_B2") (pintype "bidirectional"))
    )
    (net (code "79") (name "Net-(JP6-Pad7)") (class "Default")
      (node (ref "JP6") (pin "7") (pinfunction "7_7") (pintype "passive"))
      (node (ref "R42") (pin "2") (pinfunction "2_2") (pintype "bidirectional"))
      (node (ref "R68") (pin "2") (pinfunction "2_2") (pintype "bidirectional"))
      (node (ref "T2") (pin "B2") (pinfunction "B2_B2") (pintype "bidirectional"))
    )
    (net (code "80") (name "Net-(JP6-Pad8)") (class "Default")
      (node (ref "JP6") (pin "8") (pinfunction "8_8") (pintype "passive"))
      (node (ref "R41") (pin "2") (pinfunction "2_2") (pintype "bidirectional"))
      (node (ref "R67") (pin "2") (pinfunction "2_2") (pintype "bidirectional"))
      (node (ref "T1") (pin "B2") (pinfunction "B2_B2") (pintype "bidirectional"))
    )
    (net (code "81") (name "Net-(JP9-Pad2)") (class "Default")
      (node (ref "JP9") (pin "2") (pinfunction "2_2") (pintype "passive"))
      (node (ref "R1") (pin "2") (pinfunction "2_2") (pintype "bidirectional"))
    )
    (net (code "82") (name "Net-(JP9-Pad6)") (class "Default")
      (node (ref "JP9") (pin "6") (pinfunction "6_6") (pintype "passive"))
      (node (ref "R56") (pin "2") (pinfunction "2_2") (pintype "bidirectional"))
    )
    (net (code "83") (name "Net-(JP9-Pad8)") (class "Default")
      (node (ref "JP9") (pin "8") (pinfunction "8_8") (pintype "passive"))
      (node (ref "R55") (pin "2") (pinfunction "2_2") (pintype "bidirectional"))
    )
    (net (code "84") (name "Net-(JP14-Pad1)") (class "Default")
      (node (ref "JP14") (pin "1") (pinfunction "1_1") (pintype "passive"))
      (node (ref "R82") (pin "1") (pinfunction "1_1") (pintype "bidirectional"))
      (node (ref "R96") (pin "2") (pinfunction "2_2") (pintype "bidirectional"))
    )
    (net (code "85") (name "Net-(JP14-Pad2)") (class "Default")
      (node (ref "JP14") (pin "2") (pinfunction "2_2") (pintype "passive"))
      (node (ref "R81") (pin "1") (pinfunction "1_1") (pintype "bidirectional"))
      (node (ref "R95") (pin "2") (pinfunction "2_2") (pintype "bidirectional"))
    )
    (net (code "86") (name "Net-(JP14-Pad3)") (class "Default")
      (node (ref "JP14") (pin "3") (pinfunction "3_3") (pintype "passive"))
      (node (ref "R80") (pin "1") (pinfunction "1_1") (pintype "bidirectional"))
      (node (ref "R94") (pin "2") (pinfunction "2_2") (pintype "bidirectional"))
    )
    (net (code "87") (name "Net-(JP14-Pad4)") (class "Default")
      (node (ref "JP14") (pin "4") (pinfunction "4_4") (pintype "passive"))
      (node (ref "R79") (pin "1") (pinfunction "1_1") (pintype "bidirectional"))
      (node (ref "R93") (pin "2") (pinfunction "2_2") (pintype "bidirectional"))
    )
    (net (code "88") (name "Net-(JP14-Pad5)") (class "Default")
      (node (ref "JP14") (pin "5") (pinfunction "5_5") (pintype "passive"))
      (node (ref "R78") (pin "1") (pinfunction "1_1") (pintype "bidirectional"))
      (node (ref "R92") (pin "2") (pinfunction "2_2") (pintype "bidirectional"))
    )
    (net (code "89") (name "Net-(JP14-Pad6)") (class "Default")
      (node (ref "JP14") (pin "6") (pinfunction "6_6") (pintype "passive"))
      (node (ref "R77") (pin "1") (pinfunction "1_1") (pintype "bidirectional"))
      (node (ref "R91") (pin "2") (pinfunction "2_2") (pintype "bidirectional"))
    )
    (net (code "90") (name "Net-(JP14-Pad7)") (class "Default")
      (node (ref "JP14") (pin "7") (pinfunction "7_7") (pintype "passive"))
      (node (ref "R76") (pin "1") (pinfunction "1_1") (pintype "bidirectional"))
      (node (ref "R90") (pin "2") (pinfunction "2_2") (pintype "bidirectional"))
    )
    (net (code "91") (name "Net-(JP14-Pad8)") (class "Default")
      (node (ref "JP14") (pin "8") (pinfunction "8_8") (pintype "passive"))
      (node (ref "R54") (pin "2") (pinfunction "2_2") (pintype "bidirectional"))
      (node (ref "R75") (pin "1") (pinfunction "1_1") (pintype "bidirectional"))
    )
    (net (code "92") (name "Net-(JP15-Pad1)") (class "Default")
      (node (ref "JP15") (pin "1") (pinfunction "1_1") (pintype "passive"))
      (node (ref "R18") (pin "2") (pinfunction "2_2") (pintype "bidirectional"))
    )
    (net (code "93") (name "Net-(JP15-Pad2)") (class "Default")
      (node (ref "JP15") (pin "2") (pinfunction "2_2") (pintype "passive"))
      (node (ref "JP9") (pin "4") (pinfunction "4_4") (pintype "passive"))
      (node (ref "R16") (pin "1") (pinfunction "1_1") (pintype "bidirectional"))
      (node (ref "X1") (pin "6") (pinfunction "6_6") (pintype "passive"))
    )
    (net (code "94") (name "Net-(JP16-Pad1)") (class "Default")
      (node (ref "JP16") (pin "1") (pinfunction "1_1") (pintype "passive"))
      (node (ref "R19") (pin "2") (pinfunction "2_2") (pintype "bidirectional"))
    )
    (net (code "95") (name "Net-(JP16-Pad2)") (class "Default")
      (node (ref "JP16") (pin "2") (pinfunction "2_2") (pintype "passive"))
      (node (ref "JP9") (pin "5") (pinfunction "5_5") (pintype "passive"))
      (node (ref "R15") (pin "1") (pinfunction "1_1") (pintype "bidirectional"))
      (node (ref "X1") (pin "4") (pinfunction "4_4") (pintype "passive"))
    )
    (net (code "96") (name "Net-(JP17-Pad1)") (class "Default")
      (node (ref "JP17") (pin "1") (pinfunction "1_1") (pintype "passive"))
      (node (ref "R20") (pin "2") (pinfunction "2_2") (pintype "bidirectional"))
    )
    (net (code "97") (name "Net-(JP17-Pad2)") (class "Default")
      (node (ref "JP17") (pin "2") (pinfunction "2_2") (pintype "passive"))
      (node (ref "JP9") (pin "7") (pinfunction "7_7") (pintype "passive"))
      (node (ref "R17") (pin "1") (pinfunction "1_1") (pintype "bidirectional"))
      (node (ref "X1") (pin "3") (pinfunction "3_3") (pintype "passive"))
    )
    (net (code "98") (name "Net-(JP19-Pad2)") (class "Default")
      (node (ref "JP19") (pin "2") (pinfunction "2_2") (pintype "passive"))
      (node (ref "R47") (pin "2") (pinfunction "2_2") (pintype "bidirectional"))
      (node (ref "R57") (pin "2") (pinfunction "2_2") (pintype "bidirectional"))
      (node (ref "X12") (pin "2") (pinfunction "2_2") (pintype "passive"))
    )
    (net (code "99") (name "Net-(LD1-1)") (class "Default")
      (node (ref "LD1") (pin "K") (pinfunction "1_K") (pintype "bidirectional"))
      (node (ref "R10") (pin "2") (pinfunction "2_2") (pintype "bidirectional"))
    )
    (net (code "100") (name "Net-(LD2-1)") (class "Default")
      (node (ref "LD2") (pin "K") (pinfunction "1_K") (pintype "bidirectional"))
      (node (ref "R11") (pin "2") (pinfunction "2_2") (pintype "bidirectional"))
    )
    (net (code "101") (name "Net-(LD3-2)") (class "Default")
      (node (ref "LD3") (pin "A") (pinfunction "2_A") (pintype "bidirectional"))
      (node (ref "R27") (pin "2") (pinfunction "2_2") (pintype "bidirectional"))
    )
    (net (code "102") (name "Net-(LD4-2)") (class "Default")
      (node (ref "LD4") (pin "A") (pinfunction "2_A") (pintype "bidirectional"))
      (node (ref "R28") (pin "2") (pinfunction "2_2") (pintype "bidirectional"))
    )
    (net (code "103") (name "Net-(LD5-2)") (class "Default")
      (node (ref "LD5") (pin "A") (pinfunction "2_A") (pintype "bidirectional"))
      (node (ref "R29") (pin "2") (pinfunction "2_2") (pintype "bidirectional"))
    )
    (net (code "104") (name "Net-(LD6-2)") (class "Default")
      (node (ref "LD6") (pin "A") (pinfunction "2_A") (pintype "bidirectional"))
      (node (ref "R35") (pin "2") (pinfunction "2_2") (pintype "bidirectional"))
    )
    (net (code "105") (name "Net-(LD7-2)") (class "Default")
      (node (ref "LD7") (pin "A") (pinfunction "2_A") (pintype "bidirectional"))
      (node (ref "R36") (pin "2") (pinfunction "2_2") (pintype "bidirectional"))
    )
    (net (code "106") (name "Net-(LD8-2)") (class "Default")
      (node (ref "LD8") (pin "A") (pinfunction "2_A") (pintype "bidirectional"))
      (node (ref "R37") (pin "2") (pinfunction "2_2") (pintype "bidirectional"))
    )
    (net (code "107") (name "Net-(LD9-2)") (class "Default")
      (node (ref "LD9") (pin "A") (pinfunction "2_A") (pintype "bidirectional"))
      (node (ref "R38") (pin "2") (pinfunction "2_2") (pintype "bidirectional"))
    )
    (net (code "108") (name "Net-(LD10-2)") (class "Default")
      (node (ref "LD10") (pin "A") (pinfunction "2_A") (pintype "bidirectional"))
      (node (ref "R39") (pin "2") (pinfunction "2_2") (pintype "bidirectional"))
    )
    (net (code "109") (name "Net-(LD11-2)") (class "Default")
      (node (ref "LD11") (pin "A") (pinfunction "2_A") (pintype "bidirectional"))
      (node (ref "R75") (pin "2") (pinfunction "2_2") (pintype "bidirectional"))
    )
    (net (code "110") (name "Net-(LD12-2)") (class "Default")
      (node (ref "LD12") (pin "A") (pinfunction "2_A") (pintype "bidirectional"))
      (node (ref "R76") (pin "2") (pinfunction "2_2") (pintype "bidirectional"))
    )
    (net (code "111") (name "Net-(LD13-2)") (class "Default")
      (node (ref "LD13") (pin "A") (pinfunction "2_A") (pintype "bidirectional"))
      (node (ref "R77") (pin "2") (pinfunction "2_2") (pintype "bidirectional"))
    )
    (net (code "112") (name "Net-(LD14-2)") (class "Default")
      (node (ref "LD14") (pin "A") (pinfunction "2_A") (pintype "bidirectional"))
      (node (ref "R78") (pin "2") (pinfunction "2_2") (pintype "bidirectional"))
    )
    (net (code "113") (name "Net-(LD15-2)") (class "Default")
      (node (ref "LD15") (pin "A") (pinfunction "2_A") (pintype "bidirectional"))
      (node (ref "R79") (pin "2") (pinfunction "2_2") (pintype "bidirectional"))
    )
    (net (code "114") (name "Net-(LD16-2)") (class "Default")
      (node (ref "LD16") (pin "A") (pinfunction "2_A") (pintype "bidirectional"))
      (node (ref "R80") (pin "2") (pinfunction "2_2") (pintype "bidirectional"))
    )
    (net (code "115") (name "Net-(LD17-2)") (class "Default")
      (node (ref "LD17") (pin "A") (pinfunction "2_A") (pintype "bidirectional"))
      (node (ref "R81") (pin "2") (pinfunction "2_2") (pintype "bidirectional"))
    )
    (net (code "116") (name "Net-(LD18-2)") (class "Default")
      (node (ref "LD18") (pin "A") (pinfunction "2_A") (pintype "bidirectional"))
      (node (ref "R82") (pin "2") (pinfunction "2_2") (pintype "bidirectional"))
    )
    (net (code "117") (name "Net-(R4-Pad1)") (class "Default")
      (node (ref "R4") (pin "1") (pinfunction "1_1") (pintype "bidirectional"))
      (node (ref "X3") (pin "1") (pinfunction "1_1") (pintype "bidirectional"))
    )
    (net (code "118") (name "Net-(R5-Pad1)") (class "Default")
      (node (ref "R5") (pin "1") (pinfunction "1_1") (pintype "bidirectional"))
      (node (ref "X8") (pin "1") (pinfunction "1_1") (pintype "bidirectional"))
    )
    (net (code "119") (name "Net-(R12-Pad1)") (class "Default")
      (node (ref "R12") (pin "1") (pinfunction "1_1") (pintype "bidirectional"))
      (node (ref "X2") (pin "1") (pinfunction "1_1") (pintype "passive"))
    )
    (net (code "120") (name "Net-(R14-Pad1)") (class "Default")
      (node (ref "R14") (pin "1") (pinfunction "1_1") (pintype "bidirectional"))
      (node (ref "X1") (pin "5") (pinfunction "5_5") (pintype "passive"))
    )
    (net (code "121") (name "Net-(R22-Pad2)") (class "Default")
      (node (ref "R22") (pin "2") (pinfunction "2_2") (pintype "bidirectional"))
      (node (ref "R98") (pin "1") (pinfunction "1_1") (pintype "bidirectional"))
      (node (ref "X11") (pin "1") (pinfunction "1_1") (pintype "passive"))
    )
    (net (code "122") (name "Net-(R67-Pad1)") (class "Default")
      (node (ref "R67") (pin "1") (pinfunction "1_1") (pintype "bidirectional"))
      (node (ref "X6") (pin "1") (pinfunction "1_1") (pintype "bidirectional"))
    )
    (net (code "123") (name "Net-(R68-Pad1)") (class "Default")
      (node (ref "R68") (pin "1") (pinfunction "1_1") (pintype "bidirectional"))
      (node (ref "X6") (pin "2") (pinfunction "2_2") (pintype "bidirectional"))
    )
    (net (code "124") (name "Net-(R69-Pad1)") (class "Default")
      (node (ref "R69") (pin "1") (pinfunction "1_1") (pintype "bidirectional"))
      (node (ref "X6") (pin "3") (pinfunction "3_3") (pintype "bidirectional"))
    )
    (net (code "125") (name "Net-(R70-Pad1)") (class "Default")
      (node (ref "R70") (pin "1") (pinfunction "1_1") (pintype "bidirectional"))
      (node (ref "X6") (pin "4") (pinfunction "4_4") (pintype "bidirectional"))
    )
    (net (code "126") (name "Net-(R71-Pad1)") (class "Default")
      (node (ref "R71") (pin "1") (pinfunction "1_1") (pintype "bidirectional"))
      (node (ref "X7") (pin "1") (pinfunction "1_1") (pintype "bidirectional"))
    )
    (net (code "127") (name "Net-(R72-Pad1)") (class "Default")
      (node (ref "R72") (pin "1") (pinfunction "1_1") (pintype "bidirectional"))
      (node (ref "X7") (pin "2") (pinfunction "2_2") (pintype "bidirectional"))
    )
    (net (code "128") (name "Net-(R73-Pad1)") (class "Default")
      (node (ref "R73") (pin "1") (pinfunction "1_1") (pintype "bidirectional"))
      (node (ref "X7") (pin "3") (pinfunction "3_3") (pintype "bidirectional"))
    )
    (net (code "129") (name "Net-(R74-Pad1)") (class "Default")
      (node (ref "R74") (pin "1") (pinfunction "1_1") (pintype "bidirectional"))
      (node (ref "X7") (pin "4") (pinfunction "4_4") (pintype "bidirectional"))
    )
    (net (code "130") (name "Net-(R97-Pad2)") (class "Default")
      (node (ref "R97") (pin "2") (pinfunction "2_2") (pintype "bidirectional"))
      (node (ref "X11") (pin "2") (pinfunction "2_2") (pintype "passive"))
    )
    (net (code "131") (name "Net-(R100-Pad1)") (class "Default")
      (node (ref "R100") (pin "1") (pinfunction "1_1") (pintype "bidirectional"))
      (node (ref "R105") (pin "2") (pinfunction "2_2") (pintype "bidirectional"))
      (node (ref "X12") (pin "3") (pinfunction "3_3") (pintype "passive"))
    )
    (net (code "132") (name "Net-(R106-Pad2)") (class "Default")
      (node (ref "R106") (pin "2") (pinfunction "2_2") (pintype "bidirectional"))
      (node (ref "R99") (pin "1") (pinfunction "1_1") (pintype "bidirectional"))
      (node (ref "X12") (pin "4") (pinfunction "4_4") (pintype "passive"))
    )
    (net (code "133") (name "Net-(T10-B)") (class "Default")
      (node (ref "R51") (pin "1") (pinfunction "1_1") (pintype "bidirectional"))
      (node (ref "T10") (pin "2") (pinfunction "B_2") (pintype "passive"))
    )
    (net (code "134") (name "Net-(T10-C)") (class "Default")
      (node (ref "T10") (pin "3") (pinfunction "C_3") (pintype "passive"))
      (node (ref "X10") (pin "16") (pinfunction "K_16") (pintype "bidirectional"))
    )
    (net (code "135") (name "Net-(X10-A)") (class "Default")
      (node (ref "R53") (pin "2") (pinfunction "2_2") (pintype "bidirectional"))
      (node (ref "X10") (pin "15") (pinfunction "A_15") (pintype "bidirectional"))
    )
    (net (code "136") (name "Net-(X10-VD)") (class "Default")
      (node (ref "R52") (pin "2") (pinfunction "2_2") (pintype "passive"))
      (node (ref "X10") (pin "3") (pinfunction "VD_3") (pintype "bidirectional"))
    )
    (net (code "137") (name "Net-(XB1-DIN{slash}~{CONFIG})") (class "Default")
      (node (ref "R21") (pin "2") (pinfunction "2_2") (pintype "bidirectional"))
      (node (ref "R7") (pin "1") (pinfunction "1_1") (pintype "bidirectional"))
      (node (ref "XB1") (pin "3") (pinfunction "DIN/~{CONFIG}_3") (pintype "input"))
    )
    (net (code "138") (name "Net-(XB1-DOUT)") (class "Default")
      (node (ref "R8") (pin "2") (pinfunction "2_2") (pintype "bidirectional"))
      (node (ref "XB1") (pin "2") (pinfunction "DOUT_2") (pintype "output"))
    )
    (net (code "139") (name "Net-(XB1-~{DTR}{slash}SLEEP_RQ{slash}DI8)") (class "Default")
      (node (ref "R102") (pin "2") (pinfunction "2_2") (pintype "bidirectional"))
      (node (ref "R103") (pin "1") (pinfunction "1_1") (pintype "bidirectional"))
      (node (ref "XB1") (pin "9") (pinfunction "~{DTR}/SLEEP_RQ/DI8_9") (pintype "bidirectional"))
    )
    (net (code "140") (name "Net-(XB1-~{RTS}{slash}AD6{slash}DIO6)") (class "Default")
      (node (ref "R101") (pin "1") (pinfunction "1_1") (pintype "bidirectional"))
      (node (ref "R104") (pin "2") (pinfunction "2_2") (pintype "bidirectional"))
      (node (ref "XB1") (pin "16") (pinfunction "~{RTS}/AD6/DIO6_16") (pintype "bidirectional"))
    )
    (net (code "141") (name "RES_TFT") (class "Default")
      (node (ref "IC01") (pin "29") (pinfunction "PE6_29") (pintype "bidirectional"))
      (node (ref "R55") (pin "1") (pinfunction "1_1") (pintype "bidirectional"))
    )
    (net (code "142") (name "RTS_XBEE") (class "Default")
      (node (ref "IC01") (pin "13") (pinfunction "PF5_13") (pintype "bidirectional"))
      (node (ref "R101") (pin "2") (pinfunction "2_2") (pintype "bidirectional"))
    )
    (net (code "143") (name "RX2") (class "Default")
      (node (ref "IC01") (pin "24") (pinfunction "PF1_24") (pintype "bidirectional"))
      (node (ref "JP8") (pin "1") (pinfunction "1_1") (pintype "passive"))
      (node (ref "R22") (pin "1") (pinfunction "1_1") (pintype "bidirectional"))
      (node (ref "R8") (pin "1") (pinfunction "1_1") (pintype "bidirectional"))
    )
    (net (code "144") (name "SS{slash}") (class "Default")
      (node (ref "IC01") (pin "17") (pinfunction "PE2_17") (pintype "bidirectional"))
      (node (ref "R17") (pin "2") (pinfunction "2_2") (pintype "bidirectional"))
    )
    (net (code "145") (name "TX2") (class "Default")
      (node (ref "IC01") (pin "23") (pinfunction "PF0_23") (pintype "bidirectional"))
      (node (ref "JP8") (pin "2") (pinfunction "2_2") (pintype "passive"))
      (node (ref "R7") (pin "2") (pinfunction "2_2") (pintype "bidirectional"))
      (node (ref "R97") (pin "1") (pinfunction "1_1") (pintype "bidirectional"))
    )
    (net (code "146") (name "XTAL") (class "Default")
      (node (ref "C17") (pin "1") (pinfunction "1_1") (pintype "bidirectional"))
      (node (ref "IC01") (pin "9") (pinfunction "PG0_9") (pintype "bidirectional"))
      (node (ref "Q2") (pin "2") (pinfunction "2_2") (pintype "passive"))
      (node (ref "R50") (pin "2") (pinfunction "2_2") (pintype "bidirectional"))
    )
    (net (code "147") (name "unconnected-(IC01F-PF6-Pad14)") (class "Default")
      (node (ref "IC01") (pin "14") (pinfunction "PF6_14") (pintype "bidirectional"))
    )
    (net (code "148") (name "unconnected-(IC01F-PF7-Pad37)") (class "Default")
      (node (ref "IC01") (pin "37") (pinfunction "PF7_37") (pintype "bidirectional"))
    )
    (net (code "149") (name "unconnected-(IC01G-PG5-Pad28)") (class "Default")
      (node (ref "IC01") (pin "28") (pinfunction "PG5_28") (pintype "bidirectional"))
    )
    (net (code "150") (name "unconnected-(IC02-CBUS2-Pad13)") (class "Default")
      (node (ref "IC02") (pin "13") (pinfunction "CBUS2_13") (pintype "bidirectional"))
    )
    (net (code "151") (name "unconnected-(IC02-CBUS3-Pad14)") (class "Default")
      (node (ref "IC02") (pin "14") (pinfunction "CBUS3_14") (pintype "bidirectional"))
    )
    (net (code "152") (name "unconnected-(IC02-CBUS4-Pad12)") (class "Default")
      (node (ref "IC02") (pin "12") (pinfunction "CBUS4_12") (pintype "bidirectional"))
    )
    (net (code "153") (name "unconnected-(IC02-CTS-Pad11)") (class "Default")
      (node (ref "IC02") (pin "11") (pinfunction "CTS_11") (pintype "bidirectional"))
    )
    (net (code "154") (name "unconnected-(IC02-DCD-Pad10)") (class "Default")
      (node (ref "IC02") (pin "10") (pinfunction "DCD_10") (pintype "bidirectional"))
    )
    (net (code "155") (name "unconnected-(IC02-DSR-Pad9)") (class "Default")
      (node (ref "IC02") (pin "9") (pinfunction "DSR_9") (pintype "bidirectional"))
    )
    (net (code "156") (name "unconnected-(IC02-DTR-Pad2)") (class "Default")
      (node (ref "IC02") (pin "2") (pinfunction "DTR_2") (pintype "bidirectional"))
    )
    (net (code "157") (name "unconnected-(IC02-OSCIN-Pad27)") (class "Default")
      (node (ref "IC02") (pin "27") (pinfunction "OSCIN_27") (pintype "bidirectional"))
    )
    (net (code "158") (name "unconnected-(IC02-OSCOUT-Pad28)") (class "Default")
      (node (ref "IC02") (pin "28") (pinfunction "OSCOUT_28") (pintype "bidirectional"))
    )
    (net (code "159") (name "unconnected-(IC02-RI-Pad6)") (class "Default")
      (node (ref "IC02") (pin "6") (pinfunction "RI_6") (pintype "bidirectional"))
    )
    (net (code "160") (name "unconnected-(IC02-RTS-Pad3)") (class "Default")
      (node (ref "IC02") (pin "3") (pinfunction "RTS_3") (pintype "bidirectional"))
    )
    (net (code "161") (name "unconnected-(JP1-Pad3)") (class "Default")
      (node (ref "JP1") (pin "3") (pinfunction "3_3") (pintype "passive"))
    )
    (net (code "162") (name "unconnected-(JP1-Pad5)") (class "Default")
      (node (ref "JP1") (pin "5") (pinfunction "5_5") (pintype "passive"))
    )
    (net (code "163") (name "unconnected-(JP7-Pad1)") (class "Default")
      (node (ref "JP7") (pin "1") (pinfunction "1_1") (pintype "passive"))
    )
    (net (code "164") (name "unconnected-(JP8-Pad3)") (class "Default")
      (node (ref "JP8") (pin "3") (pinfunction "3_3") (pintype "passive"))
    )
    (net (code "165") (name "unconnected-(POT1-PadC1)") (class "Default")
      (node (ref "POT1") (pin "C1") (pinfunction "C1_C1") (pintype "bidirectional"))
    )
    (net (code "166") (name "unconnected-(POT1-PadC2)") (class "Default")
      (node (ref "POT1") (pin "C2") (pinfunction "C2_C2") (pintype "bidirectional"))
    )
    (net (code "167") (name "unconnected-(POT2-PadC1)") (class "Default")
      (node (ref "POT2") (pin "C1") (pinfunction "C1_C1") (pintype "bidirectional"))
    )
    (net (code "168") (name "unconnected-(POT2-PadC2)") (class "Default")
      (node (ref "POT2") (pin "C2") (pinfunction "C2_C2") (pintype "bidirectional"))
    )
    (net (code "169") (name "unconnected-(POT3-PadC1)") (class "Default")
      (node (ref "POT3") (pin "C1") (pinfunction "C1_C1") (pintype "bidirectional"))
    )
    (net (code "170") (name "unconnected-(POT3-PadC2)") (class "Default")
      (node (ref "POT3") (pin "C2") (pinfunction "C2_C2") (pintype "bidirectional"))
    )
    (net (code "171") (name "unconnected-(POT4-PadC1)") (class "Default")
      (node (ref "POT4") (pin "C1") (pinfunction "C1_C1") (pintype "bidirectional"))
    )
    (net (code "172") (name "unconnected-(POT4-PadC2)") (class "Default")
      (node (ref "POT4") (pin "C2") (pinfunction "C2_C2") (pintype "bidirectional"))
    )
    (net (code "173") (name "unconnected-(T1-PadA2)") (class "Default")
      (node (ref "T1") (pin "A2") (pinfunction "A2_A2") (pintype "bidirectional"))
    )
    (net (code "174") (name "unconnected-(T1-PadB1)") (class "Default")
      (node (ref "T1") (pin "B1") (pinfunction "B1_B1") (pintype "bidirectional"))
    )
    (net (code "175") (name "unconnected-(T2-PadA2)") (class "Default")
      (node (ref "T2") (pin "A2") (pinfunction "A2_A2") (pintype "bidirectional"))
    )
    (net (code "176") (name "unconnected-(T2-PadB1)") (class "Default")
      (node (ref "T2") (pin "B1") (pinfunction "B1_B1") (pintype "bidirectional"))
    )
    (net (code "177") (name "unconnected-(T3-PadA2)") (class "Default")
      (node (ref "T3") (pin "A2") (pinfunction "A2_A2") (pintype "bidirectional"))
    )
    (net (code "178") (name "unconnected-(T3-PadB1)") (class "Default")
      (node (ref "T3") (pin "B1") (pinfunction "B1_B1") (pintype "bidirectional"))
    )
    (net (code "179") (name "unconnected-(T4-PadA2)") (class "Default")
      (node (ref "T4") (pin "A2") (pinfunction "A2_A2") (pintype "bidirectional"))
    )
    (net (code "180") (name "unconnected-(T4-PadB1)") (class "Default")
      (node (ref "T4") (pin "B1") (pinfunction "B1_B1") (pintype "bidirectional"))
    )
    (net (code "181") (name "unconnected-(T5-PadA2)") (class "Default")
      (node (ref "T5") (pin "A2") (pinfunction "A2_A2") (pintype "bidirectional"))
    )
    (net (code "182") (name "unconnected-(T5-PadB1)") (class "Default")
      (node (ref "T5") (pin "B1") (pinfunction "B1_B1") (pintype "bidirectional"))
    )
    (net (code "183") (name "unconnected-(T6-PadA2)") (class "Default")
      (node (ref "T6") (pin "A2") (pinfunction "A2_A2") (pintype "bidirectional"))
    )
    (net (code "184") (name "unconnected-(T6-PadB1)") (class "Default")
      (node (ref "T6") (pin "B1") (pinfunction "B1_B1") (pintype "bidirectional"))
    )
    (net (code "185") (name "unconnected-(T7-PadA2)") (class "Default")
      (node (ref "T7") (pin "A2") (pinfunction "A2_A2") (pintype "bidirectional"))
    )
    (net (code "186") (name "unconnected-(T7-PadB1)") (class "Default")
      (node (ref "T7") (pin "B1") (pinfunction "B1_B1") (pintype "bidirectional"))
    )
    (net (code "187") (name "unconnected-(T8-PadA2)") (class "Default")
      (node (ref "T8") (pin "A2") (pinfunction "A2_A2") (pintype "bidirectional"))
    )
    (net (code "188") (name "unconnected-(T8-PadB1)") (class "Default")
      (node (ref "T8") (pin "B1") (pinfunction "B1_B1") (pintype "bidirectional"))
    )
    (net (code "189") (name "unconnected-(X2-Pad4)") (class "Default")
      (node (ref "X2") (pin "4") (pinfunction "4_4") (pintype "passive"))
    )
    (net (code "190") (name "unconnected-(XB1-AD0{slash}DIO0-Pad20)") (class "Default")
      (node (ref "XB1") (pin "20") (pinfunction "AD0/DIO0_20") (pintype "bidirectional"))
    )
    (net (code "191") (name "unconnected-(XB1-AD1{slash}DIO1-Pad19)") (class "Default")
      (node (ref "XB1") (pin "19") (pinfunction "AD1/DIO1_19") (pintype "bidirectional"))
    )
    (net (code "192") (name "unconnected-(XB1-AD2{slash}DIO2-Pad18)") (class "Default")
      (node (ref "XB1") (pin "18") (pinfunction "AD2/DIO2_18") (pintype "bidirectional"))
    )
    (net (code "193") (name "unconnected-(XB1-ASSOC{slash}AD5{slash}DIO5-Pad15)") (class "Default")
      (node (ref "XB1") (pin "15") (pinfunction "ASSOC/AD5/DIO5_15") (pintype "bidirectional"))
    )
    (net (code "194") (name "unconnected-(XB1-CD{slash}DOUT_EN{slash}DO8-Pad4)") (class "Default")
      (node (ref "XB1") (pin "4") (pinfunction "CD/DOUT_EN/DO8_4") (pintype "output"))
    )
    (net (code "195") (name "unconnected-(XB1-COORD_SEL{slash}AD3{slash}DIO3-Pad17)") (class "Default")
      (node (ref "XB1") (pin "17") (pinfunction "COORD_SEL/AD3/DIO3_17") (pintype "bidirectional"))
    )
    (net (code "196") (name "unconnected-(XB1-ON{slash}~{SLEEP}-Pad13)") (class "Default")
      (node (ref "XB1") (pin "13") (pinfunction "ON/~{SLEEP}_13") (pintype "output"))
    )
    (net (code "197") (name "unconnected-(XB1-PWM0{slash}RSSI-Pad6)") (class "Default")
      (node (ref "XB1") (pin "6") (pinfunction "PWM0/RSSI_6") (pintype "output"))
    )
    (net (code "198") (name "unconnected-(XB1-RF_TX{slash}AD4{slash}DIO4-Pad11)") (class "Default")
      (node (ref "XB1") (pin "11") (pinfunction "RF_TX/AD4/DIO4_11") (pintype "bidirectional"))
    )
    (net (code "199") (name "unconnected-(XB1-VREF-Pad14)") (class "Default")
      (node (ref "XB1") (pin "14") (pinfunction "VREF_14") (pintype "input"))
    )
    (net (code "200") (name "unconnected-(XB1-~{CTS}{slash}DIO7-Pad12)") (class "Default")
      (node (ref "XB1") (pin "12") (pinfunction "~{CTS}/DIO7_12") (pintype "bidirectional"))
    )
    (net (code "201") (name "unconnected-(XB1-~{RESET}-Pad5)") (class "Default")
      (node (ref "XB1") (pin "5") (pinfunction "~{RESET}_5") (pintype "input"))
    )
  )
)
